# 8ModuleBoard_vr2.net
KiCad netlist of a schematic drawn in EAGLE
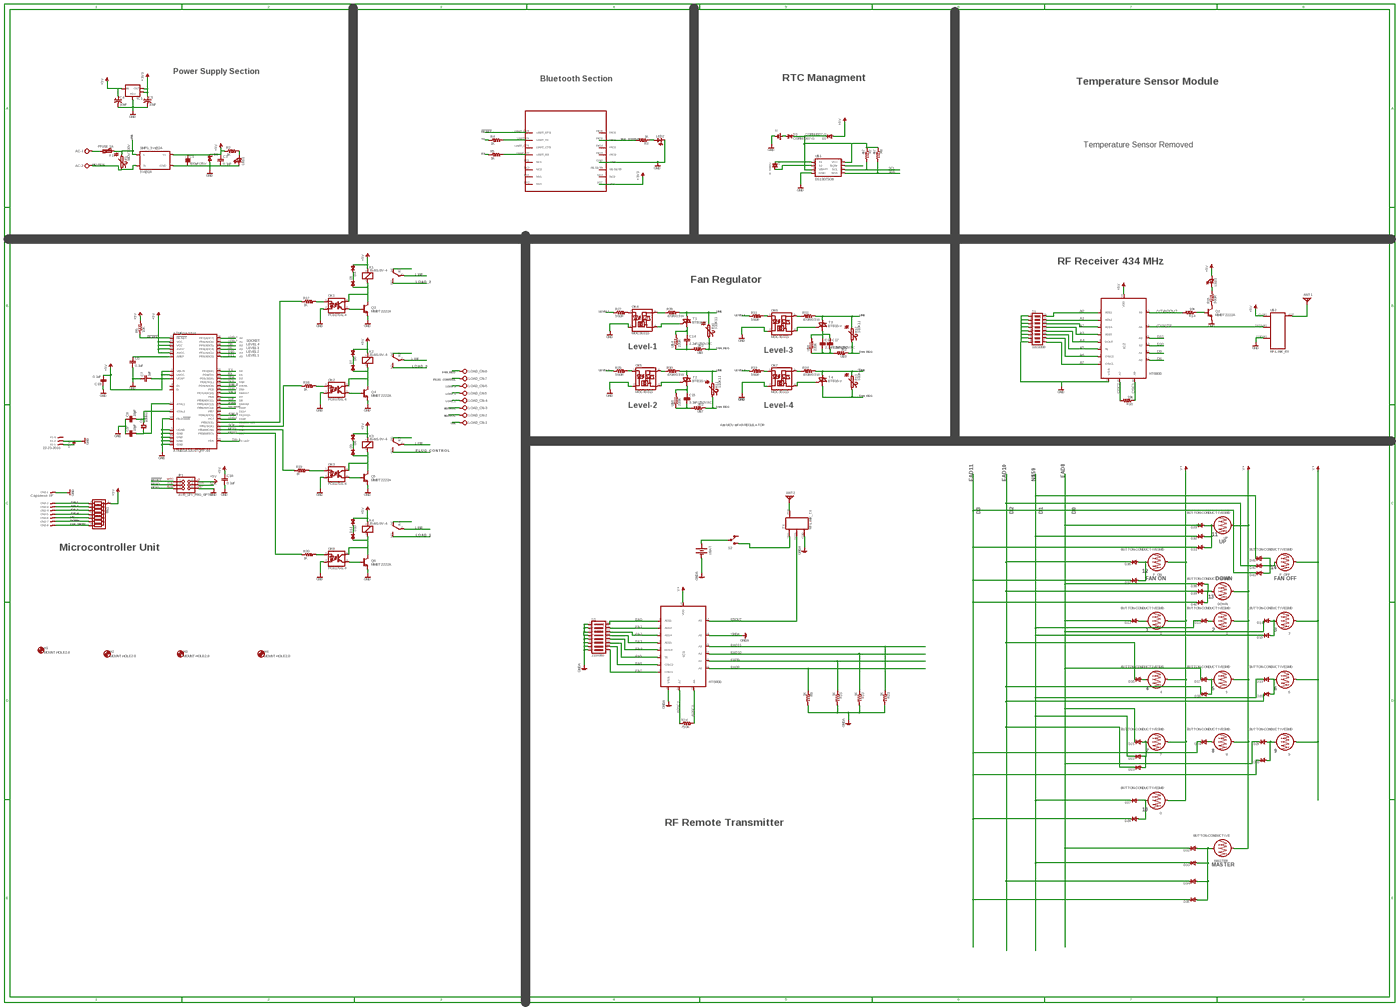
[diagram p0: schematic, sheet 1, overview]
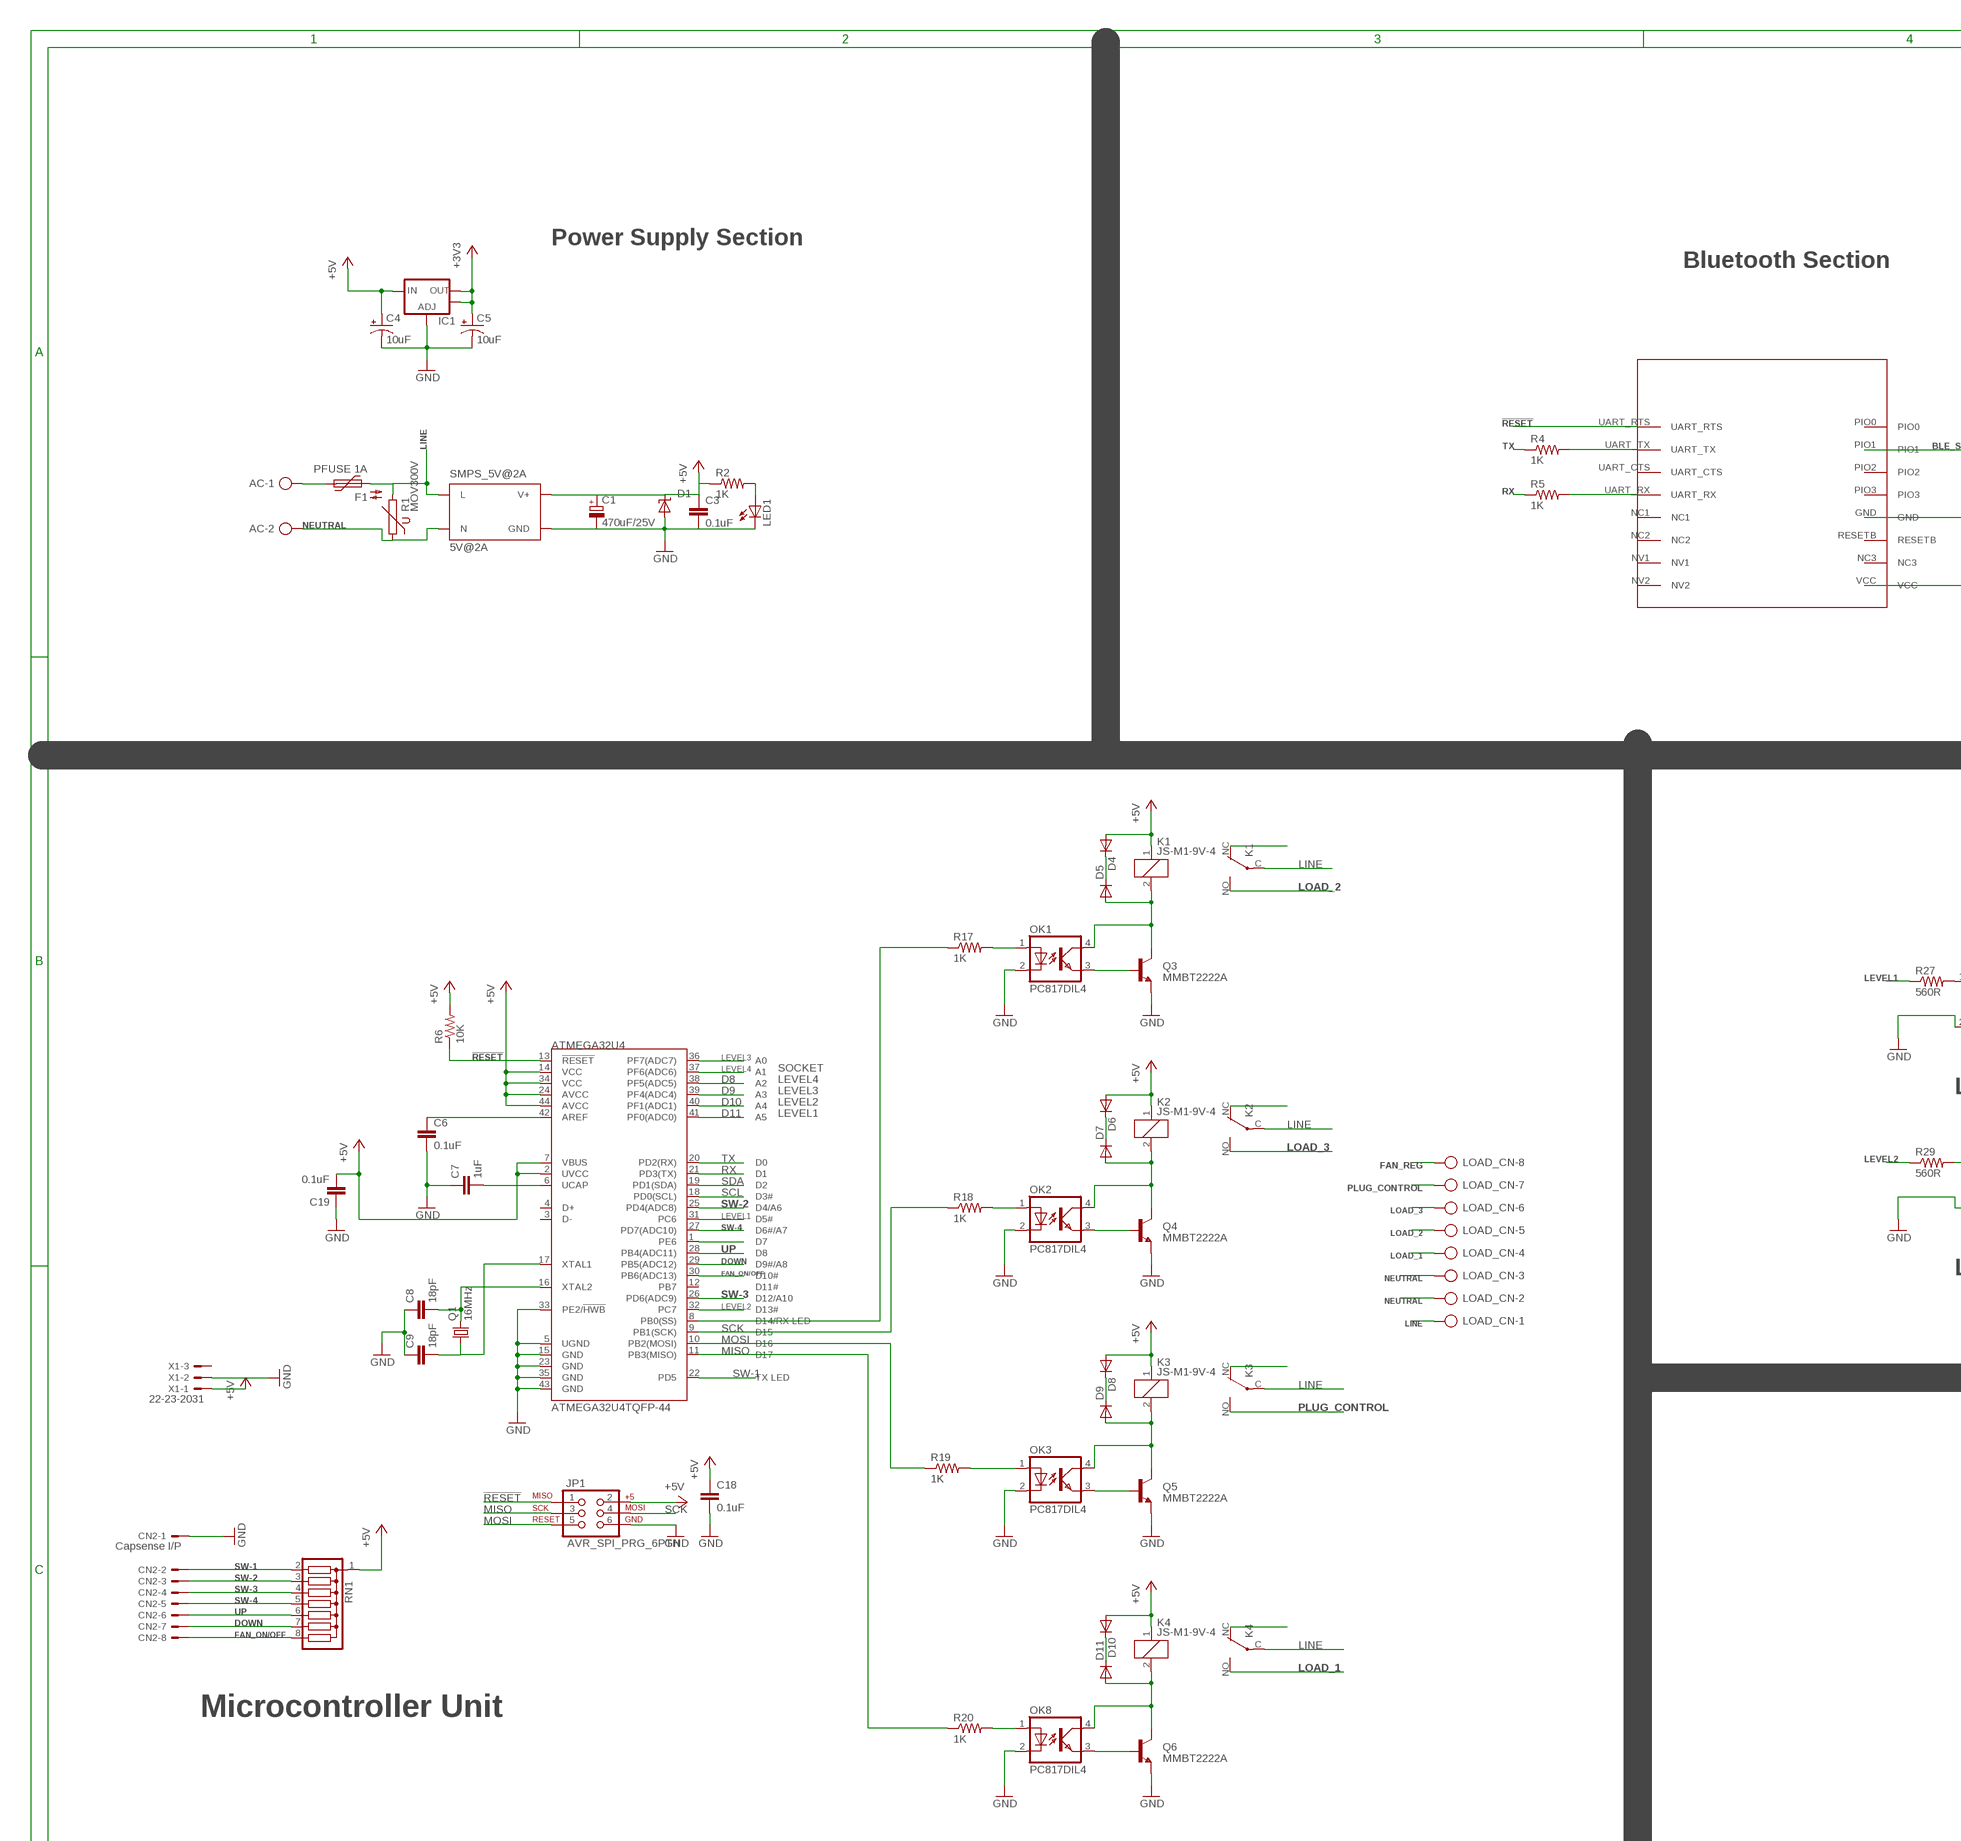
[diagram p1: schematic, sheet 1, part 1 of 4]
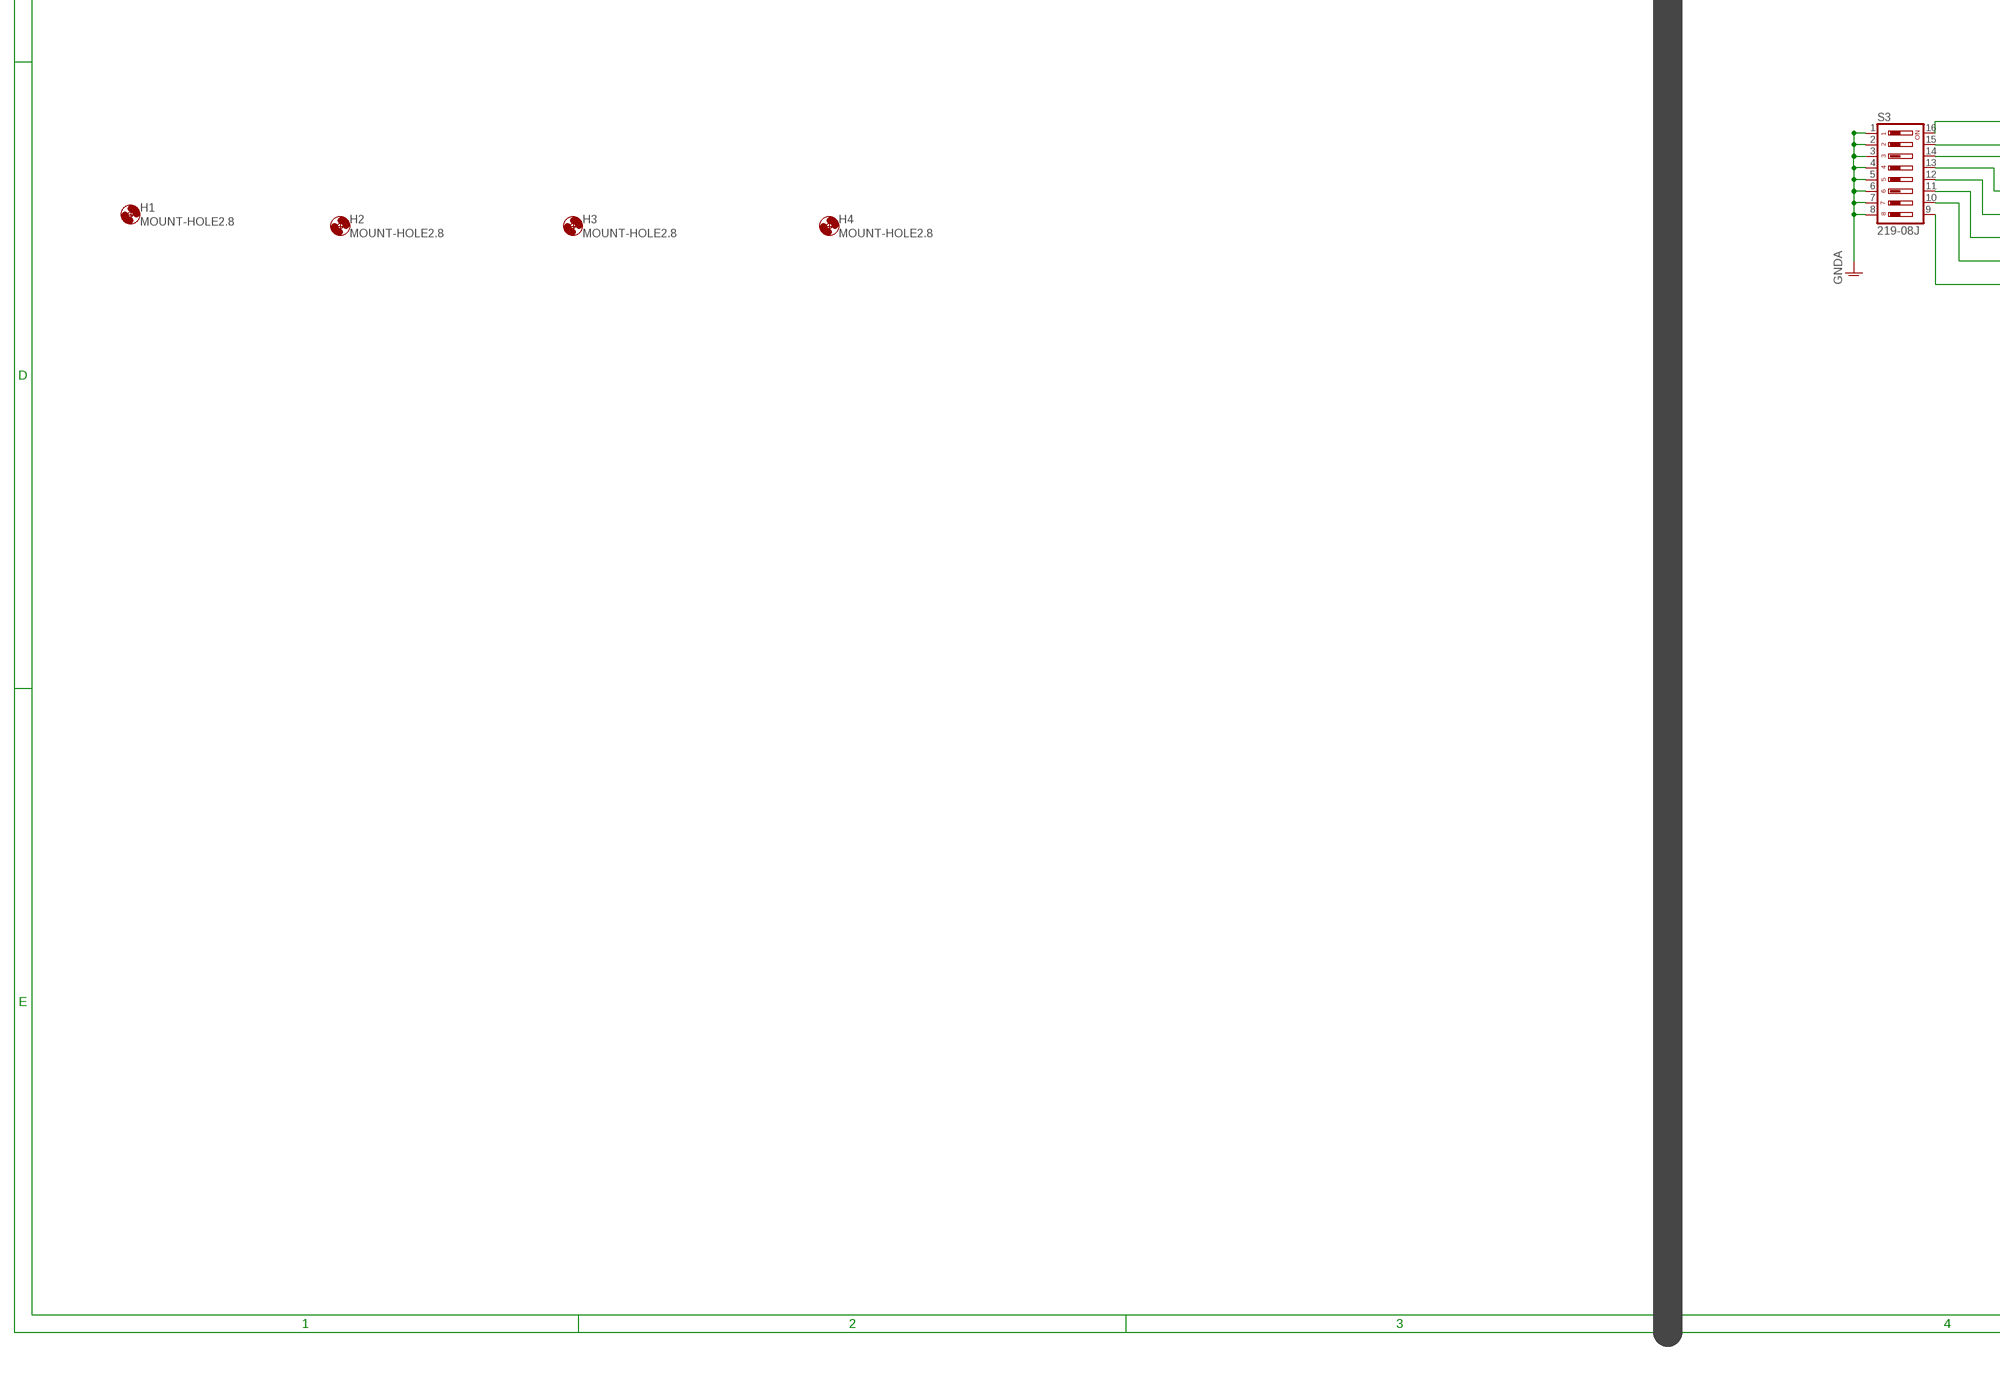
[diagram p2: schematic, sheet 1, part 2 of 4]
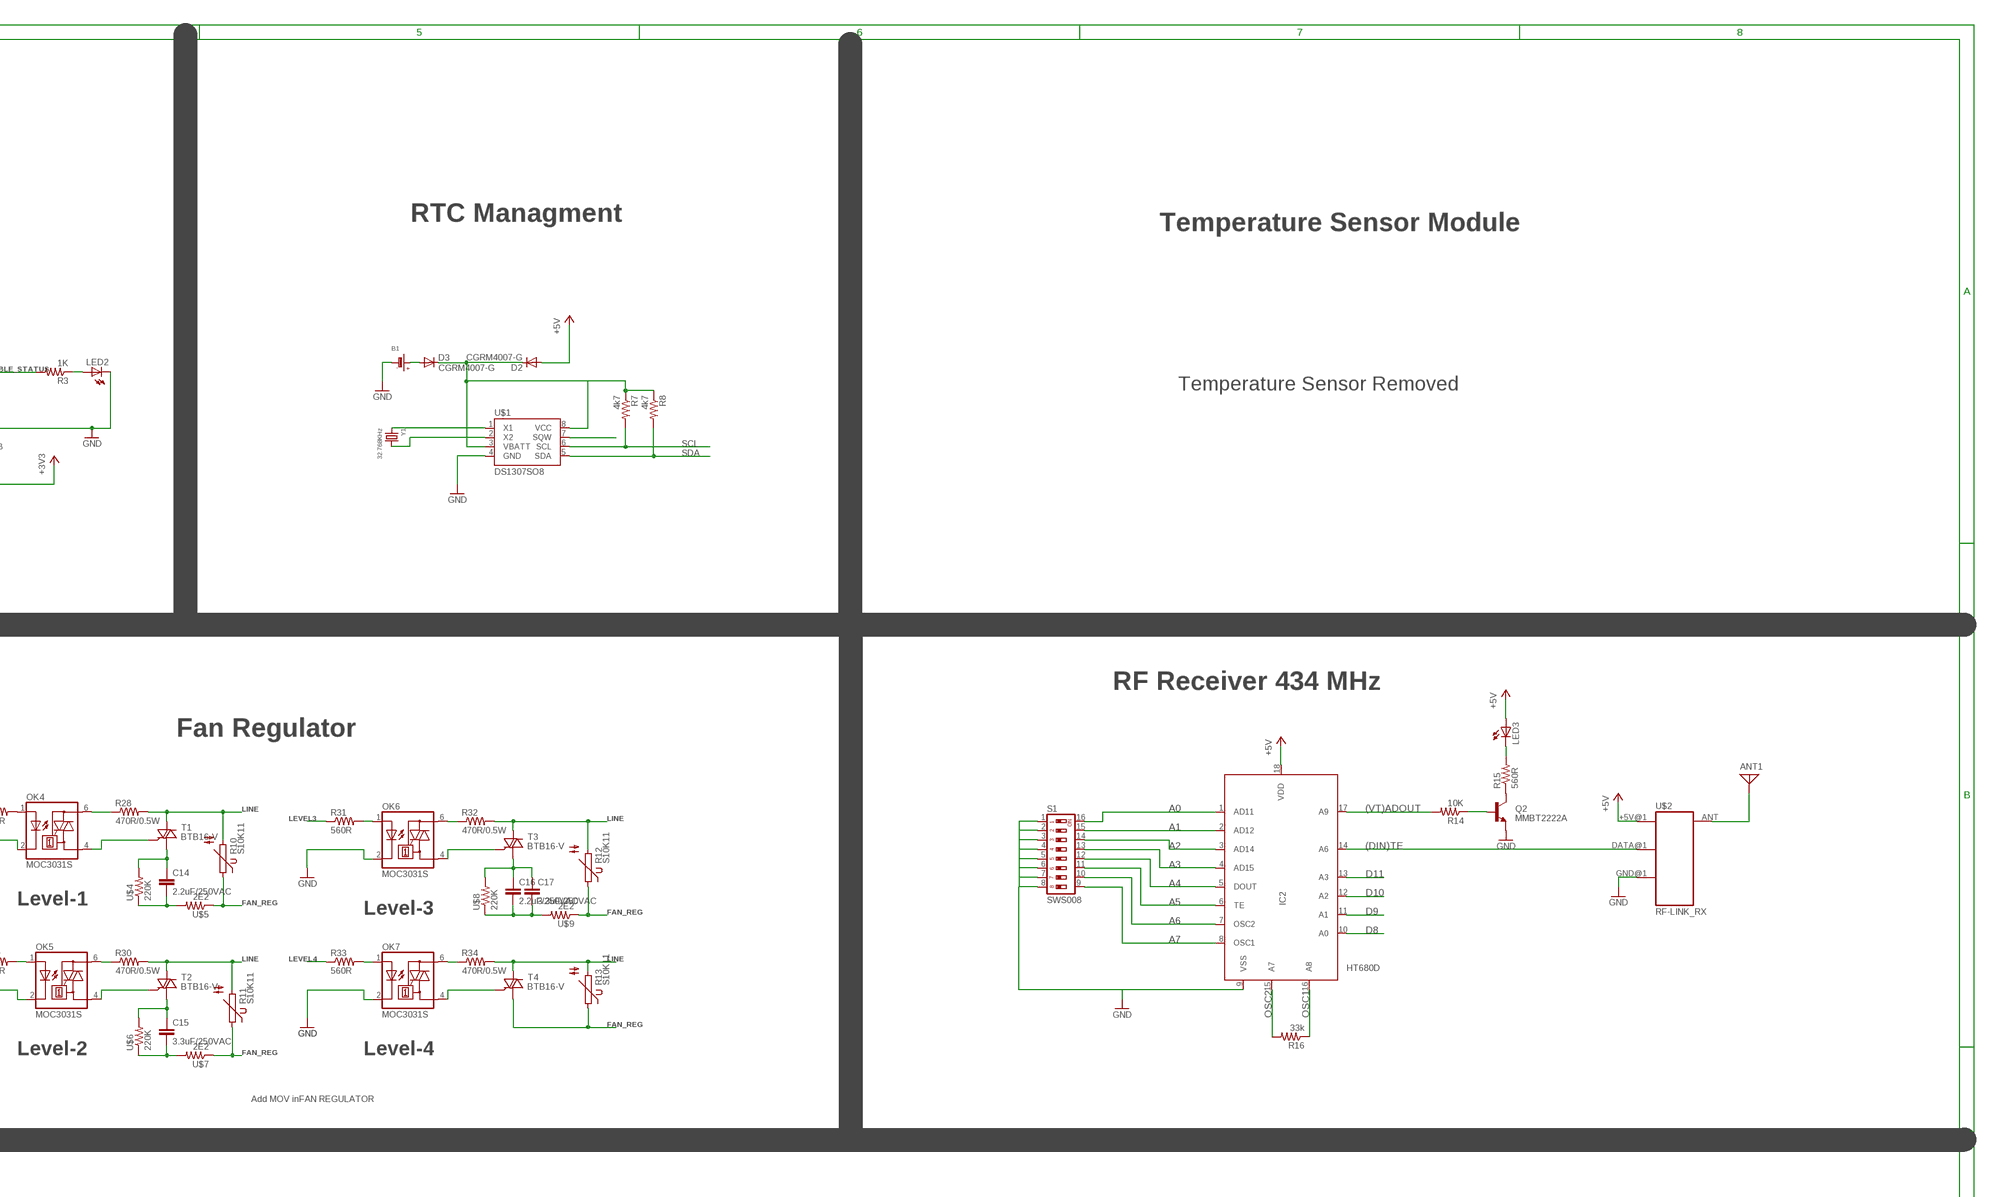
[diagram p3: schematic, sheet 1, part 3 of 4]
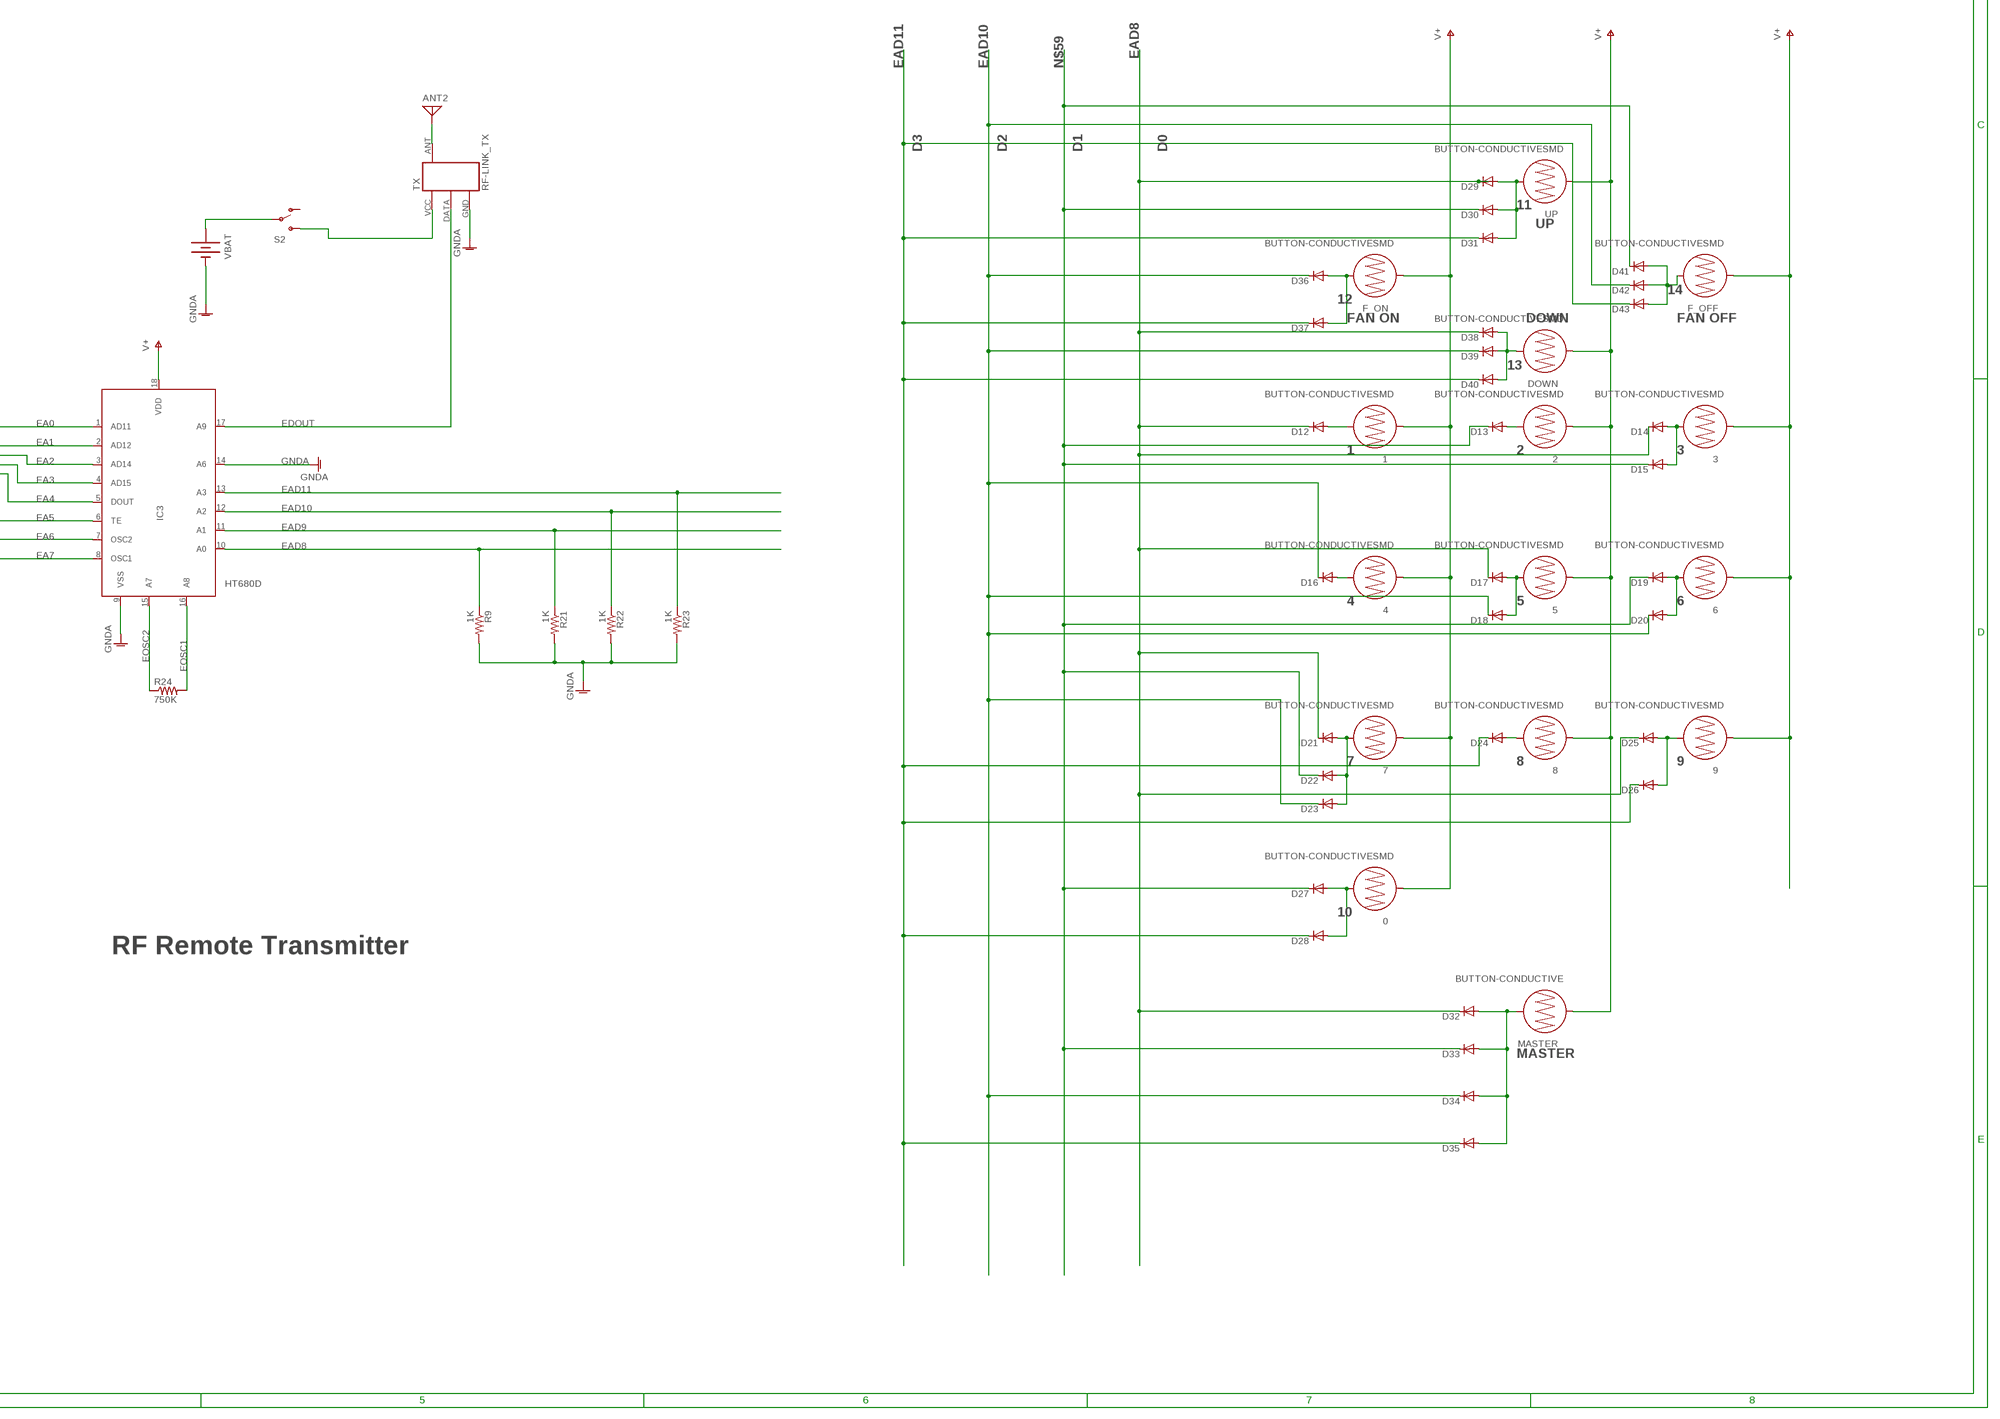
[diagram p4: schematic, sheet 1, part 4 of 4]

(export (version "E")
  (design (tool "Eeschema 10.0.6"))
  (components
    (comp (ref "0")
      (value "BUTTON-CONDUCTIVESMD")
      (footprint "eagle-import:BUTTON-CONDUCTIVE")
      (libsource (lib "eagle-import") (part "BUTTON-CONDUCTIVESMD"))
    )
    (comp (ref "1")
      (value "BUTTON-CONDUCTIVESMD")
      (footprint "eagle-import:BUTTON-CONDUCTIVE")
      (libsource (lib "eagle-import") (part "BUTTON-CONDUCTIVESMD"))
    )
    (comp (ref "2")
      (value "BUTTON-CONDUCTIVESMD")
      (footprint "eagle-import:BUTTON-CONDUCTIVE")
      (libsource (lib "eagle-import") (part "BUTTON-CONDUCTIVESMD"))
    )
    (comp (ref "3")
      (value "BUTTON-CONDUCTIVESMD")
      (footprint "eagle-import:BUTTON-CONDUCTIVE")
      (libsource (lib "eagle-import") (part "BUTTON-CONDUCTIVESMD"))
    )
    (comp (ref "4")
      (value "BUTTON-CONDUCTIVESMD")
      (footprint "eagle-import:BUTTON-CONDUCTIVE")
      (libsource (lib "eagle-import") (part "BUTTON-CONDUCTIVESMD"))
    )
    (comp (ref "5")
      (value "BUTTON-CONDUCTIVESMD")
      (footprint "eagle-import:BUTTON-CONDUCTIVE")
      (libsource (lib "eagle-import") (part "BUTTON-CONDUCTIVESMD"))
    )
    (comp (ref "6")
      (value "BUTTON-CONDUCTIVESMD")
      (footprint "eagle-import:BUTTON-CONDUCTIVE")
      (libsource (lib "eagle-import") (part "BUTTON-CONDUCTIVESMD"))
    )
    (comp (ref "7")
      (value "BUTTON-CONDUCTIVESMD")
      (footprint "eagle-import:BUTTON-CONDUCTIVE")
      (libsource (lib "eagle-import") (part "BUTTON-CONDUCTIVESMD"))
    )
    (comp (ref "8")
      (value "BUTTON-CONDUCTIVESMD")
      (footprint "eagle-import:BUTTON-CONDUCTIVE")
      (libsource (lib "eagle-import") (part "BUTTON-CONDUCTIVESMD"))
    )
    (comp (ref "9")
      (value "BUTTON-CONDUCTIVESMD")
      (footprint "eagle-import:BUTTON-CONDUCTIVE")
      (libsource (lib "eagle-import") (part "BUTTON-CONDUCTIVESMD"))
    )
    (comp (ref "AC")
      (value "AK300/2")
      (footprint "eagle-import:AK300_2")
      (libsource (lib "eagle-import") (part "AK300/2"))
    )
    (comp (ref "ANT1")
      (value "ANTENNA")
      (footprint "eagle-import:PAD-01")
      (libsource (lib "eagle-import") (part "ANTENNA"))
    )
    (comp (ref "ANT2")
      (value "ANTENNA")
      (footprint "eagle-import:PAD-01")
      (libsource (lib "eagle-import") (part "ANTENNA"))
    )
    (comp (ref "ATMEGA32U4")
      (value "ATMEGA32U4TQFP-44")
      (footprint "eagle-import:TQFP44")
      (libsource (lib "eagle-import") (part "ATMEGA32U4TQFP-44"))
    )
    (comp (ref "B1")
      (value "BATTERYCR2032")
      (footprint "eagle-import:CR2032")
      (libsource (lib "eagle-import") (part "BATTERYCR2032"))
    )
    (comp (ref "C1")
      (value "470uF/25V")
      (footprint "eagle-import:E5-8,5")
      (libsource (lib "eagle-import") (part "CPOL-EUE5-8.5"))
    )
    (comp (ref "C3")
      (value "0.1uF")
      (footprint "eagle-import:1206")
      (libsource (lib "eagle-import") (part "1.0UF50V10%(1206)"))
    )
    (comp (ref "C4")
      (value "10uF")
      (footprint "eagle-import:EIA3216")
      (libsource (lib "eagle-import") (part "10UF-16V-10%(TANT)"))
    )
    (comp (ref "C5")
      (value "10uF")
      (footprint "eagle-import:EIA3216")
      (libsource (lib "eagle-import") (part "10UF-16V-10%(TANT)"))
    )
    (comp (ref "C6")
      (value "0.1uF")
      (footprint "eagle-import:1206")
      (libsource (lib "eagle-import") (part "CAP1206"))
    )
    (comp (ref "C7")
      (value "1uF")
      (footprint "eagle-import:1206")
      (libsource (lib "eagle-import") (part "CAP1206"))
    )
    (comp (ref "C8")
      (value "18pF")
      (footprint "eagle-import:1206")
      (libsource (lib "eagle-import") (part "CAP1206"))
    )
    (comp (ref "C9")
      (value "18pF")
      (footprint "eagle-import:1206")
      (libsource (lib "eagle-import") (part "CAP1206"))
    )
    (comp (ref "C14")
      (value "2.2uF/250VAC")
      (footprint "eagle-import:C27.5B9")
      (libsource (lib "eagle-import") (part "C27/9"))
    )
    (comp (ref "C15")
      (value "3.3uF/250VAC")
      (footprint "eagle-import:C27.5B9")
      (libsource (lib "eagle-import") (part "C27/9"))
    )
    (comp (ref "C16")
      (value "2.2uF/250VAC")
      (footprint "eagle-import:C27.5B9")
      (libsource (lib "eagle-import") (part "C27/9"))
    )
    (comp (ref "C17")
      (value "3.3uF/250VAC")
      (footprint "eagle-import:C27.5B9")
      (libsource (lib "eagle-import") (part "C27/9"))
    )
    (comp (ref "C18")
      (value "0.1uF")
      (footprint "eagle-import:1206")
      (libsource (lib "eagle-import") (part "CAP1206"))
    )
    (comp (ref "C19")
      (value "0.1uF")
      (footprint "eagle-import:1206")
      (libsource (lib "eagle-import") (part "CAP1206"))
    )
    (comp (ref "CN2")
      (value "Capsense I/P")
      (footprint "eagle-import:22-23-2081")
      (fields (field (name "MF") "MOLEX") (field (name "MPN") "22-23-2081"))
      (libsource (lib "eagle-import") (part "22-23-2081"))
    )
    (comp (ref "D1")
      (value "SUPPRESSOR-SMBJ")
      (footprint "eagle-import:SMBJ")
      (libsource (lib "eagle-import") (part "SUPPRESSOR-SMBJ"))
    )
    (comp (ref "D2")
      (value "CGRM4007-G")
      (footprint "eagle-import:SOD-123_MINI-SMA")
      (libsource (lib "eagle-import") (part "CGRM400-G7"))
    )
    (comp (ref "D3")
      (value "CGRM4007-G")
      (footprint "eagle-import:SOD-123_MINI-SMA")
      (libsource (lib "eagle-import") (part "CGRM400-G7"))
    )
    (comp (ref "D4")
      (value "DIODE-SOD123")
      (footprint "eagle-import:SOD123")
      (libsource (lib "eagle-import") (part "DIODE-SOD123"))
    )
    (comp (ref "D5")
      (value "DIODE-SOD123")
      (footprint "eagle-import:SOD123")
      (libsource (lib "eagle-import") (part "DIODE-SOD123"))
    )
    (comp (ref "D6")
      (value "DIODE-SOD123")
      (footprint "eagle-import:SOD123")
      (libsource (lib "eagle-import") (part "DIODE-SOD123"))
    )
    (comp (ref "D7")
      (value "DIODE-SOD123")
      (footprint "eagle-import:SOD123")
      (libsource (lib "eagle-import") (part "DIODE-SOD123"))
    )
    (comp (ref "D8")
      (value "DIODE-SOD123")
      (footprint "eagle-import:SOD123")
      (libsource (lib "eagle-import") (part "DIODE-SOD123"))
    )
    (comp (ref "D9")
      (value "DIODE-SOD123")
      (footprint "eagle-import:SOD123")
      (libsource (lib "eagle-import") (part "DIODE-SOD123"))
    )
    (comp (ref "D10")
      (value "DIODE-SOD123")
      (footprint "eagle-import:SOD123")
      (libsource (lib "eagle-import") (part "DIODE-SOD123"))
    )
    (comp (ref "D11")
      (value "DIODE-SOD123")
      (footprint "eagle-import:SOD123")
      (libsource (lib "eagle-import") (part "DIODE-SOD123"))
    )
    (comp (ref "D12")
      (value "DIODE-SOD123")
      (footprint "eagle-import:SOD123")
      (libsource (lib "eagle-import") (part "DIODE-SOD123"))
    )
    (comp (ref "D13")
      (value "DIODE-SOD123")
      (footprint "eagle-import:SOD123")
      (libsource (lib "eagle-import") (part "DIODE-SOD123"))
    )
    (comp (ref "D14")
      (value "DIODE-SOD123")
      (footprint "eagle-import:SOD123")
      (libsource (lib "eagle-import") (part "DIODE-SOD123"))
    )
    (comp (ref "D15")
      (value "DIODE-SOD123")
      (footprint "eagle-import:SOD123")
      (libsource (lib "eagle-import") (part "DIODE-SOD123"))
    )
    (comp (ref "D16")
      (value "DIODE-SOD123")
      (footprint "eagle-import:SOD123")
      (libsource (lib "eagle-import") (part "DIODE-SOD123"))
    )
    (comp (ref "D17")
      (value "DIODE-SOD123")
      (footprint "eagle-import:SOD123")
      (libsource (lib "eagle-import") (part "DIODE-SOD123"))
    )
    (comp (ref "D18")
      (value "DIODE-SOD123")
      (footprint "eagle-import:SOD123")
      (libsource (lib "eagle-import") (part "DIODE-SOD123"))
    )
    (comp (ref "D19")
      (value "DIODE-SOD123")
      (footprint "eagle-import:SOD123")
      (libsource (lib "eagle-import") (part "DIODE-SOD123"))
    )
    (comp (ref "D20")
      (value "DIODE-SOD123")
      (footprint "eagle-import:SOD123")
      (libsource (lib "eagle-import") (part "DIODE-SOD123"))
    )
    (comp (ref "D21")
      (value "DIODE-SOD123")
      (footprint "eagle-import:SOD123")
      (libsource (lib "eagle-import") (part "DIODE-SOD123"))
    )
    (comp (ref "D22")
      (value "DIODE-SOD123")
      (footprint "eagle-import:SOD123")
      (libsource (lib "eagle-import") (part "DIODE-SOD123"))
    )
    (comp (ref "D23")
      (value "DIODE-SOD123")
      (footprint "eagle-import:SOD123")
      (libsource (lib "eagle-import") (part "DIODE-SOD123"))
    )
    (comp (ref "D24")
      (value "DIODE-SOD123")
      (footprint "eagle-import:SOD123")
      (libsource (lib "eagle-import") (part "DIODE-SOD123"))
    )
    (comp (ref "D25")
      (value "DIODE-SOD123")
      (footprint "eagle-import:SOD123")
      (libsource (lib "eagle-import") (part "DIODE-SOD123"))
    )
    (comp (ref "D26")
      (value "DIODE-SOD123")
      (footprint "eagle-import:SOD123")
      (libsource (lib "eagle-import") (part "DIODE-SOD123"))
    )
    (comp (ref "D27")
      (value "DIODE-SOD123")
      (footprint "eagle-import:SOD123")
      (libsource (lib "eagle-import") (part "DIODE-SOD123"))
    )
    (comp (ref "D28")
      (value "DIODE-SOD123")
      (footprint "eagle-import:SOD123")
      (libsource (lib "eagle-import") (part "DIODE-SOD123"))
    )
    (comp (ref "D29")
      (value "DIODE-SOD123")
      (footprint "eagle-import:SOD123")
      (libsource (lib "eagle-import") (part "DIODE-SOD123"))
    )
    (comp (ref "D30")
      (value "DIODE-SOD123")
      (footprint "eagle-import:SOD123")
      (libsource (lib "eagle-import") (part "DIODE-SOD123"))
    )
    (comp (ref "D31")
      (value "DIODE-SOD123")
      (footprint "eagle-import:SOD123")
      (libsource (lib "eagle-import") (part "DIODE-SOD123"))
    )
    (comp (ref "D32")
      (value "DIODE-SOD123")
      (footprint "eagle-import:SOD123")
      (libsource (lib "eagle-import") (part "DIODE-SOD123"))
    )
    (comp (ref "D33")
      (value "DIODE-SOD123")
      (footprint "eagle-import:SOD123")
      (libsource (lib "eagle-import") (part "DIODE-SOD123"))
    )
    (comp (ref "D34")
      (value "DIODE-SOD123")
      (footprint "eagle-import:SOD123")
      (libsource (lib "eagle-import") (part "DIODE-SOD123"))
    )
    (comp (ref "D35")
      (value "DIODE-SOD123")
      (footprint "eagle-import:SOD123")
      (libsource (lib "eagle-import") (part "DIODE-SOD123"))
    )
    (comp (ref "D36")
      (value "DIODE-SOD123")
      (footprint "eagle-import:SOD123")
      (libsource (lib "eagle-import") (part "DIODE-SOD123"))
    )
    (comp (ref "D37")
      (value "DIODE-SOD123")
      (footprint "eagle-import:SOD123")
      (libsource (lib "eagle-import") (part "DIODE-SOD123"))
    )
    (comp (ref "D38")
      (value "DIODE-SOD123")
      (footprint "eagle-import:SOD123")
      (libsource (lib "eagle-import") (part "DIODE-SOD123"))
    )
    (comp (ref "D39")
      (value "DIODE-SOD123")
      (footprint "eagle-import:SOD123")
      (libsource (lib "eagle-import") (part "DIODE-SOD123"))
    )
    (comp (ref "D40")
      (value "DIODE-SOD123")
      (footprint "eagle-import:SOD123")
      (libsource (lib "eagle-import") (part "DIODE-SOD123"))
    )
    (comp (ref "D41")
      (value "DIODE-SOD123")
      (footprint "eagle-import:SOD123")
      (libsource (lib "eagle-import") (part "DIODE-SOD123"))
    )
    (comp (ref "D42")
      (value "DIODE-SOD123")
      (footprint "eagle-import:SOD123")
      (libsource (lib "eagle-import") (part "DIODE-SOD123"))
    )
    (comp (ref "D43")
      (value "DIODE-SOD123")
      (footprint "eagle-import:SOD123")
      (libsource (lib "eagle-import") (part "DIODE-SOD123"))
    )
    (comp (ref "DOWN")
      (value "BUTTON-CONDUCTIVESMD")
      (footprint "eagle-import:BUTTON-CONDUCTIVE")
      (libsource (lib "eagle-import") (part "BUTTON-CONDUCTIVESMD"))
    )
    (comp (ref "F1")
      (value "PFUSE 1A")
      (footprint "eagle-import:MF-5,1B")
      (libsource (lib "eagle-import") (part "MF-R055-5,1B"))
    )
    (comp (ref "F_OFF")
      (value "BUTTON-CONDUCTIVESMD")
      (footprint "eagle-import:BUTTON-CONDUCTIVE")
      (libsource (lib "eagle-import") (part "BUTTON-CONDUCTIVESMD"))
    )
    (comp (ref "F_ON")
      (value "BUTTON-CONDUCTIVESMD")
      (footprint "eagle-import:BUTTON-CONDUCTIVE")
      (libsource (lib "eagle-import") (part "BUTTON-CONDUCTIVESMD"))
    )
    (comp (ref "H1")
      (value "MOUNT-HOLE2.8")
      (footprint "eagle-import:2,8")
      (libsource (lib "eagle-import") (part "MOUNT-HOLE2.8"))
    )
    (comp (ref "H2")
      (value "MOUNT-HOLE2.8")
      (footprint "eagle-import:2,8")
      (libsource (lib "eagle-import") (part "MOUNT-HOLE2.8"))
    )
    (comp (ref "H3")
      (value "MOUNT-HOLE2.8")
      (footprint "eagle-import:2,8")
      (libsource (lib "eagle-import") (part "MOUNT-HOLE2.8"))
    )
    (comp (ref "H4")
      (value "MOUNT-HOLE2.8")
      (footprint "eagle-import:2,8")
      (libsource (lib "eagle-import") (part "MOUNT-HOLE2.8"))
    )
    (comp (ref "IC1")
      (value "V_REG_LM1117SOT223")
      (footprint "eagle-import:SOT223")
      (libsource (lib "eagle-import") (part "V_REG_LM1117SOT223"))
    )
    (comp (ref "IC2")
      (value "HT680D")
      (footprint "eagle-import:SOP18")
      (libsource (lib "eagle-import") (part "HT680D"))
    )
    (comp (ref "IC3")
      (value "HT680D")
      (footprint "eagle-import:SOP18")
      (libsource (lib "eagle-import") (part "HT680D"))
    )
    (comp (ref "JP1")
      (value "AVR_SPI_PRG_6PTH")
      (footprint "eagle-import:2X3")
      (libsource (lib "eagle-import") (part "AVR_SPI_PRG_6PTH"))
    )
    (comp (ref "K1")
      (value "JS-M1-9V-4")
      (footprint "eagle-import:JS-M")
      (libsource (lib "eagle-import") (part "JS-M1-9V-4"))
    )
    (comp (ref "K2")
      (value "JS-M1-9V-4")
      (footprint "eagle-import:JS-M")
      (libsource (lib "eagle-import") (part "JS-M1-9V-4"))
    )
    (comp (ref "K3")
      (value "JS-M1-9V-4")
      (footprint "eagle-import:JS-M")
      (libsource (lib "eagle-import") (part "JS-M1-9V-4"))
    )
    (comp (ref "K4")
      (value "JS-M1-9V-4")
      (footprint "eagle-import:JS-M")
      (libsource (lib "eagle-import") (part "JS-M1-9V-4"))
    )
    (comp (ref "LED1")
      (value "LEDSML1206")
      (footprint "eagle-import:SML1206")
      (libsource (lib "eagle-import") (part "LEDSML1206"))
    )
    (comp (ref "LED2")
      (value "LEDSML1206")
      (footprint "eagle-import:SML1206")
      (libsource (lib "eagle-import") (part "LEDSML1206"))
    )
    (comp (ref "LED3")
      (value "LEDSML1206")
      (footprint "eagle-import:SML1206")
      (libsource (lib "eagle-import") (part "LEDSML1206"))
    )
    (comp (ref "LOAD_CN")
      (value "AK300/8")
      (footprint "eagle-import:AK300_8")
      (libsource (lib "eagle-import") (part "AK300/8"))
    )
    (comp (ref "MASTER")
      (value "BUTTON-CONDUCTIVE")
      (footprint "eagle-import:BUTTON-CONDUCTIVE-MINI")
      (libsource (lib "eagle-import") (part "BUTTON-CONDUCTIVE"))
    )
    (comp (ref "OK1")
      (value "PC817DIL4")
      (footprint "eagle-import:DIL4-SMD")
      (libsource (lib "eagle-import") (part "PC817DIL4"))
    )
    (comp (ref "OK2")
      (value "PC817DIL4")
      (footprint "eagle-import:DIL4-SMD")
      (libsource (lib "eagle-import") (part "PC817DIL4"))
    )
    (comp (ref "OK3")
      (value "PC817DIL4")
      (footprint "eagle-import:DIL4-SMD")
      (libsource (lib "eagle-import") (part "PC817DIL4"))
    )
    (comp (ref "OK4")
      (value "MOC3031S")
      (footprint "eagle-import:DIL6-SMD")
      (fields (field (name "MF") "FAIRCHILD SEMICONDUCTOR") (field (name "MPN") "MOC3031SM"))
      (libsource (lib "eagle-import") (part "MOC30S31"))
    )
    (comp (ref "OK5")
      (value "MOC3031S")
      (footprint "eagle-import:DIL6-SMD")
      (fields
        (field (name "MF") "FAIRCHILD SEMICONDUCTOR")
        (field (name "MPN") "MOC3031SM")
        (field (name "MF_1") "FAIRCHILD SEMICONDUCTOR")
        (field (name "MPN_1") "MOC3031SM")
        (field (name "OC_FARNELL") "unknown")
        (field (name "OC_NEWARK") "34C1335")
      )
      (libsource (lib "eagle-import") (part "MOC30S31"))
    )
    (comp (ref "OK6")
      (value "MOC3031S")
      (footprint "eagle-import:DIL6-SMD")
      (fields
        (field (name "MF") "FAIRCHILD SEMICONDUCTOR")
        (field (name "MPN") "MOC3031SM")
        (field (name "MF_1") "FAIRCHILD SEMICONDUCTOR")
        (field (name "MPN_1") "MOC3031SM")
        (field (name "OC_FARNELL") "unknown")
        (field (name "OC_NEWARK") "34C1335")
      )
      (libsource (lib "eagle-import") (part "MOC30S31"))
    )
    (comp (ref "OK7")
      (value "MOC3031S")
      (footprint "eagle-import:DIL6-SMD")
      (fields
        (field (name "MF") "FAIRCHILD SEMICONDUCTOR")
        (field (name "MPN") "MOC3031SM")
        (field (name "MF_1") "FAIRCHILD SEMICONDUCTOR")
        (field (name "MPN_1") "MOC3031SM")
        (field (name "OC_FARNELL") "unknown")
        (field (name "OC_NEWARK") "34C1335")
      )
      (libsource (lib "eagle-import") (part "MOC30S31"))
    )
    (comp (ref "OK8")
      (value "PC817DIL4")
      (footprint "eagle-import:DIL4-SMD")
      (libsource (lib "eagle-import") (part "PC817DIL4"))
    )
    (comp (ref "Q1")
      (value "16MHz")
      (footprint "eagle-import:HC49UP")
      (libsource (lib "eagle-import") (part "CRYSTALHC49UP"))
    )
    (comp (ref "Q2")
      (value "MMBT2222A")
      (footprint "eagle-import:SOT23-3")
      (libsource (lib "eagle-import") (part "TRANSISTOR_NPNMMBT2222A"))
    )
    (comp (ref "Q3")
      (value "MMBT2222A")
      (footprint "eagle-import:SOT23-3")
      (fields (field (name "PROD_ID") "TRANS-08049"))
      (libsource (lib "eagle-import") (part "TRANSISTOR_NPNMMBT2222A"))
    )
    (comp (ref "Q4")
      (value "MMBT2222A")
      (footprint "eagle-import:SOT23-3")
      (fields (field (name "PROD_ID") "TRANS-08049"))
      (libsource (lib "eagle-import") (part "TRANSISTOR_NPNMMBT2222A"))
    )
    (comp (ref "Q5")
      (value "MMBT2222A")
      (footprint "eagle-import:SOT23-3")
      (fields (field (name "PROD_ID") "TRANS-08049"))
      (libsource (lib "eagle-import") (part "TRANSISTOR_NPNMMBT2222A"))
    )
    (comp (ref "Q6")
      (value "MMBT2222A")
      (footprint "eagle-import:SOT23-3")
      (fields (field (name "PROD_ID") "TRANS-08049"))
      (libsource (lib "eagle-import") (part "TRANSISTOR_NPNMMBT2222A"))
    )
    (comp (ref "R1")
      (value "MOV300V")
      (footprint "eagle-import:S10K11")
      (libsource (lib "eagle-import") (part "S10K11"))
    )
    (comp (ref "R2")
      (value "1K")
      (footprint "eagle-import:1206")
      (libsource (lib "eagle-import") (part "SparkFun-Resistors_RESISTOR1206"))
    )
    (comp (ref "R3")
      (value "1K")
      (footprint "eagle-import:1206")
      (libsource (lib "eagle-import") (part "RESISTOR1206"))
    )
    (comp (ref "R4")
      (value "1K")
      (footprint "eagle-import:1206")
      (libsource (lib "eagle-import") (part "SparkFun-Resistors_RESISTOR1206"))
    )
    (comp (ref "R5")
      (value "1K")
      (footprint "eagle-import:1206")
      (libsource (lib "eagle-import") (part "SparkFun-Resistors_RESISTOR1206"))
    )
    (comp (ref "R6")
      (value "10K")
      (footprint "eagle-import:1206")
      (libsource (lib "eagle-import") (part "RESISTOR1206"))
    )
    (comp (ref "R7")
      (value "4k7")
      (footprint "eagle-import:1206")
      (libsource (lib "eagle-import") (part "RESISTOR1206"))
    )
    (comp (ref "R8")
      (value "4k7")
      (footprint "eagle-import:1206")
      (libsource (lib "eagle-import") (part "RESISTOR1206"))
    )
    (comp (ref "R9")
      (value "1K")
      (footprint "eagle-import:1206")
      (libsource (lib "eagle-import") (part "RESISTOR1206"))
    )
    (comp (ref "R10")
      (value "S10K11")
      (footprint "eagle-import:S10K11")
      (libsource (lib "eagle-import") (part "S10K11"))
    )
    (comp (ref "R11")
      (value "S10K11")
      (footprint "eagle-import:S10K11")
      (libsource (lib "eagle-import") (part "S10K11"))
    )
    (comp (ref "R12")
      (value "S10K11")
      (footprint "eagle-import:S10K11")
      (libsource (lib "eagle-import") (part "S10K11"))
    )
    (comp (ref "R13")
      (value "S10K11")
      (footprint "eagle-import:S10K11")
      (libsource (lib "eagle-import") (part "S10K11"))
    )
    (comp (ref "R14")
      (value "10K")
      (footprint "eagle-import:1206")
      (libsource (lib "eagle-import") (part "RESISTOR1206"))
    )
    (comp (ref "R15")
      (value "560R")
      (footprint "eagle-import:1206")
      (libsource (lib "eagle-import") (part "SparkFun-Resistors_RESISTOR1206"))
    )
    (comp (ref "R16")
      (value "33k")
      (footprint "eagle-import:1206")
      (libsource (lib "eagle-import") (part "SparkFun-Resistors_RESISTOR1206"))
    )
    (comp (ref "R17")
      (value "1K")
      (footprint "eagle-import:1206")
      (libsource (lib "eagle-import") (part "SparkFun-Resistors_RESISTOR1206"))
    )
    (comp (ref "R18")
      (value "1K")
      (footprint "eagle-import:1206")
      (libsource (lib "eagle-import") (part "SparkFun-Resistors_RESISTOR1206"))
    )
    (comp (ref "R19")
      (value "1K")
      (footprint "eagle-import:1206")
      (libsource (lib "eagle-import") (part "SparkFun-Resistors_RESISTOR1206"))
    )
    (comp (ref "R20")
      (value "1K")
      (footprint "eagle-import:1206")
      (libsource (lib "eagle-import") (part "SparkFun-Resistors_RESISTOR1206"))
    )
    (comp (ref "R21")
      (value "1K")
      (footprint "eagle-import:1206")
      (libsource (lib "eagle-import") (part "RESISTOR1206"))
    )
    (comp (ref "R22")
      (value "1K")
      (footprint "eagle-import:1206")
      (libsource (lib "eagle-import") (part "RESISTOR1206"))
    )
    (comp (ref "R23")
      (value "1K")
      (footprint "eagle-import:1206")
      (libsource (lib "eagle-import") (part "RESISTOR1206"))
    )
    (comp (ref "R24")
      (value "750K")
      (footprint "eagle-import:1206")
      (libsource (lib "eagle-import") (part "RESISTOR1206"))
    )
    (comp (ref "R27")
      (value "560R")
      (footprint "eagle-import:1206")
      (libsource (lib "eagle-import") (part "SparkFun-Resistors_RESISTOR1206"))
    )
    (comp (ref "R28")
      (value "470R/0.5W")
      (footprint "eagle-import:0411V")
      (libsource (lib "eagle-import") (part "R-US_0411/3V"))
    )
    (comp (ref "R29")
      (value "560R")
      (footprint "eagle-import:1206")
      (libsource (lib "eagle-import") (part "SparkFun-Resistors_RESISTOR1206"))
    )
    (comp (ref "R30")
      (value "470R/0.5W")
      (footprint "eagle-import:0411V")
      (libsource (lib "eagle-import") (part "R-US_0411/3V"))
    )
    (comp (ref "R31")
      (value "560R")
      (footprint "eagle-import:1206")
      (libsource (lib "eagle-import") (part "SparkFun-Resistors_RESISTOR1206"))
    )
    (comp (ref "R32")
      (value "470R/0.5W")
      (footprint "eagle-import:0411V")
      (libsource (lib "eagle-import") (part "R-US_0411/3V"))
    )
    (comp (ref "R33")
      (value "560R")
      (footprint "eagle-import:1206")
      (libsource (lib "eagle-import") (part "SparkFun-Resistors_RESISTOR1206"))
    )
    (comp (ref "R34")
      (value "470R/0.5W")
      (footprint "eagle-import:0411V")
      (libsource (lib "eagle-import") (part "R-US_0411/3V"))
    )
    (comp (ref "RN1")
      (value "G07R")
      (footprint "eagle-import:SIL8")
      (libsource (lib "eagle-import") (part "G07R"))
    )
    (comp (ref "S1")
      (value "SWS008")
      (footprint "eagle-import:SMS-008")
      (libsource (lib "eagle-import") (part "SWS008"))
    )
    (comp (ref "S2")
      (value "SWITCH-SPDT-SMD-A")
      (footprint "eagle-import:SWITCH-SPST-SMD-A")
      (libsource (lib "eagle-import") (part "SWITCH-SPDT-SMD-A"))
    )
    (comp (ref "S3")
      (value "219-08J")
      (footprint "eagle-import:CTS-219-08J")
      (libsource (lib "eagle-import") (part "219-08J"))
    )
    (comp (ref "SMPS_5V@2A")
      (value "5V@2A")
      (footprint "eagle-import:MKS1854-6-0-404")
      (libsource (lib "eagle-import") (part "MKS1854-6-0-404"))
    )
    (comp (ref "T1")
      (value "BTB16-V")
      (footprint "eagle-import:TO220BV")
      (libsource (lib "eagle-import") (part "BT138-V"))
    )
    (comp (ref "T2")
      (value "BTB16-V")
      (footprint "eagle-import:TO220BV")
      (libsource (lib "eagle-import") (part "BT138-V"))
    )
    (comp (ref "T3")
      (value "BTB16-V")
      (footprint "eagle-import:TO220BV")
      (libsource (lib "eagle-import") (part "BT138-V"))
    )
    (comp (ref "T4")
      (value "BTB16-V")
      (footprint "eagle-import:TO220BV")
      (libsource (lib "eagle-import") (part "BT138-V"))
    )
    (comp (ref "TX")
      (value "RF-LINK_TX")
      (footprint "eagle-import:RF-LINK_TX")
      (libsource (lib "eagle-import") (part "RF-LINK_TX"))
    )
    (comp (ref "U$1")
      (value "DS1307SO8")
      (footprint "eagle-import:SO08")
      (libsource (lib "eagle-import") (part "DS1307SO8"))
    )
    (comp (ref "U$2")
      (value "RF-LINK_RX")
      (footprint "eagle-import:RF-LINK_RX")
      (libsource (lib "eagle-import") (part "RF-LINK_RX"))
    )
    (comp (ref "U$3")
      (value "HM-11")
      (footprint "eagle-import:HM-11")
      (libsource (lib "eagle-import") (part "HM-11"))
    )
    (comp (ref "U$4")
      (value "220K")
      (footprint "eagle-import:1206")
      (libsource (lib "eagle-import") (part "SparkFun-Resistors_RESISTOR1206"))
    )
    (comp (ref "U$5")
      (value "2E2")
      (footprint "eagle-import:1206")
      (libsource (lib "eagle-import") (part "SparkFun-Resistors_RESISTOR1206"))
    )
    (comp (ref "U$6")
      (value "220K")
      (footprint "eagle-import:1206")
      (libsource (lib "eagle-import") (part "SparkFun-Resistors_RESISTOR1206"))
    )
    (comp (ref "U$7")
      (value "2E2")
      (footprint "eagle-import:1206")
      (libsource (lib "eagle-import") (part "SparkFun-Resistors_RESISTOR1206"))
    )
    (comp (ref "U$8")
      (value "220K")
      (footprint "eagle-import:1206")
      (libsource (lib "eagle-import") (part "SparkFun-Resistors_RESISTOR1206"))
    )
    (comp (ref "U$9")
      (value "2E2")
      (footprint "eagle-import:1206")
      (libsource (lib "eagle-import") (part "SparkFun-Resistors_RESISTOR1206"))
    )
    (comp (ref "UP")
      (value "BUTTON-CONDUCTIVESMD")
      (footprint "eagle-import:BUTTON-CONDUCTIVE")
      (libsource (lib "eagle-import") (part "BUTTON-CONDUCTIVESMD"))
    )
    (comp (ref "VBAT")
      (value "BATTERY20SMD")
      (footprint "eagle-import:BATTCON_20MM")
      (libsource (lib "eagle-import") (part "BATTERY20SMD"))
    )
    (comp (ref "X1")
      (value "22-23-2031")
      (footprint "eagle-import:22-23-2031")
      (fields (field (name "MF") "MOLEX"))
      (libsource (lib "eagle-import") (part "22-23-2031"))
    )
    (comp (ref "Y1")
      (value "32.768KHz")
      (footprint "eagle-import:CRYSTAL_CYL_2X6MM_SMT")
      (libsource (lib "eagle-import") (part "CRYSTAL32.768"))
    )
  )
  (nets
    (net (code "1") (name "+3V3") (class "Default")
      (node (ref "C5") (pin "A") (pinfunction "+_A") (pintype "passive"))
      (node (ref "IC1") (pin "2") (pinfunction "OUT_2") (pintype "output"))
      (node (ref "IC1") (pin "4") (pinfunction "OUT_4") (pintype "output"))
      (node (ref "U$3") (pin "VCC") (pinfunction "VCC_VCC") (pintype "bidirectional"))
    )
    (net (code "2") (name "+5V") (class "Default")
      (node (ref "ATMEGA32U4") (pin "14") (pinfunction "VCC_14") (pintype "bidirectional"))
      (node (ref "ATMEGA32U4") (pin "2") (pinfunction "UVCC_2") (pintype "bidirectional"))
      (node (ref "ATMEGA32U4") (pin "24") (pinfunction "AVCC_24") (pintype "bidirectional"))
      (node (ref "ATMEGA32U4") (pin "34") (pinfunction "VCC_34") (pintype "bidirectional"))
      (node (ref "ATMEGA32U4") (pin "44") (pinfunction "AVCC_44") (pintype "bidirectional"))
      (node (ref "ATMEGA32U4") (pin "7") (pinfunction "VBUS_7") (pintype "bidirectional"))
      (node (ref "C1") (pin "+") (pinfunction "+_+") (pintype "passive"))
      (node (ref "C18") (pin "1") (pinfunction "1_1") (pintype "passive"))
      (node (ref "C19") (pin "2") (pinfunction "2_2") (pintype "passive"))
      (node (ref "C3") (pin "1") (pinfunction "1_1") (pintype "passive"))
      (node (ref "C4") (pin "A") (pinfunction "+_A") (pintype "passive"))
      (node (ref "D1") (pin "C") (pinfunction "C_C") (pintype "passive"))
      (node (ref "D10") (pin "A") (pinfunction "A_A") (pintype "passive"))
      (node (ref "D2") (pin "A") (pinfunction "A_A") (pintype "passive"))
      (node (ref "D4") (pin "A") (pinfunction "A_A") (pintype "passive"))
      (node (ref "D6") (pin "A") (pinfunction "A_A") (pintype "passive"))
      (node (ref "D8") (pin "A") (pinfunction "A_A") (pintype "passive"))
      (node (ref "IC1") (pin "3") (pinfunction "IN_3") (pintype "input"))
      (node (ref "IC2") (pin "18") (pinfunction "VDD_18") (pintype "power_in"))
      (node (ref "JP1") (pin "2") (pinfunction "2_2") (pintype "passive"))
      (node (ref "K1") (pin "1") (pinfunction "1_1") (pintype "passive"))
      (node (ref "K2") (pin "1") (pinfunction "1_1") (pintype "passive"))
      (node (ref "K3") (pin "1") (pinfunction "1_1") (pintype "passive"))
      (node (ref "K4") (pin "1") (pinfunction "1_1") (pintype "passive"))
      (node (ref "LED3") (pin "A") (pinfunction "A_A") (pintype "passive"))
      (node (ref "R2") (pin "1") (pinfunction "1_1") (pintype "passive"))
      (node (ref "R6") (pin "2") (pinfunction "2_2") (pintype "passive"))
      (node (ref "RN1") (pin "1") (pinfunction "1_1") (pintype "passive"))
      (node (ref "SMPS_5V@2A") (pin "3") (pinfunction "V+_3") (pintype "input"))
      (node (ref "U$2") (pin "+5V@1") (pinfunction "+5V_+5V@1") (pintype "power_in"))
      (node (ref "X1") (pin "1") (pinfunction "S_1") (pintype "passive"))
    )
    (net (code "3") (name "/(DIN)TE") (class "Default")
      (node (ref "IC2") (pin "14") (pinfunction "A6_14") (pintype "input"))
      (node (ref "U$2") (pin "DATA@1") (pinfunction "DATA_DATA@1") (pintype "input"))
    )
    (net (code "4") (name "/(VT)ADOUT") (class "Default")
      (node (ref "IC2") (pin "17") (pinfunction "A9_17") (pintype "input"))
      (node (ref "R14") (pin "2") (pinfunction "2_2") (pintype "passive"))
    )
    (net (code "5") (name "/A0") (class "Default")
      (node (ref "IC2") (pin "1") (pinfunction "AD11_1") (pintype "input"))
      (node (ref "S1") (pin "16") (pinfunction "16_16") (pintype "passive"))
    )
    (net (code "6") (name "/A1") (class "Default")
      (node (ref "IC2") (pin "2") (pinfunction "AD12_2") (pintype "input"))
      (node (ref "S1") (pin "15") (pinfunction "15_15") (pintype "passive"))
    )
    (net (code "7") (name "/A2") (class "Default")
      (node (ref "IC2") (pin "3") (pinfunction "AD14_3") (pintype "input"))
      (node (ref "S1") (pin "14") (pinfunction "14_14") (pintype "passive"))
    )
    (net (code "8") (name "/A3") (class "Default")
      (node (ref "IC2") (pin "4") (pinfunction "AD15_4") (pintype "input"))
      (node (ref "S1") (pin "13") (pinfunction "13_13") (pintype "passive"))
    )
    (net (code "9") (name "/A4") (class "Default")
      (node (ref "IC2") (pin "5") (pinfunction "DOUT_5") (pintype "input"))
      (node (ref "S1") (pin "12") (pinfunction "12_12") (pintype "passive"))
    )
    (net (code "10") (name "/A5") (class "Default")
      (node (ref "IC2") (pin "6") (pinfunction "TE_6") (pintype "input"))
      (node (ref "S1") (pin "11") (pinfunction "11_11") (pintype "passive"))
    )
    (net (code "11") (name "/A6") (class "Default")
      (node (ref "IC2") (pin "7") (pinfunction "OSC2_7") (pintype "output"))
      (node (ref "S1") (pin "10") (pinfunction "10_10") (pintype "passive"))
    )
    (net (code "12") (name "/A7") (class "Default")
      (node (ref "IC2") (pin "8") (pinfunction "OSC1_8") (pintype "input"))
      (node (ref "S1") (pin "9") (pinfunction "9_9") (pintype "passive"))
    )
    (net (code "13") (name "/BLE_STATUS") (class "Default")
      (node (ref "R3") (pin "2") (pinfunction "2_2") (pintype "passive"))
      (node (ref "U$3") (pin "PIO1") (pinfunction "PIO1_PIO1") (pintype "bidirectional"))
    )
    (net (code "14") (name "/D8") (class "Default")
      (node (ref "ATMEGA32U4") (pin "38") (pinfunction "PF5(ADC5)_38") (pintype "bidirectional"))
      (node (ref "IC2") (pin "10") (pinfunction "A0_10") (pintype "input"))
    )
    (net (code "15") (name "/D9") (class "Default")
      (node (ref "ATMEGA32U4") (pin "39") (pinfunction "PF4(ADC4)_39") (pintype "bidirectional"))
      (node (ref "IC2") (pin "11") (pinfunction "A1_11") (pintype "input"))
    )
    (net (code "16") (name "/D10") (class "Default")
      (node (ref "ATMEGA32U4") (pin "40") (pinfunction "PF1(ADC1)_40") (pintype "bidirectional"))
      (node (ref "IC2") (pin "12") (pinfunction "A2_12") (pintype "input"))
    )
    (net (code "17") (name "/D11") (class "Default")
      (node (ref "ATMEGA32U4") (pin "41") (pinfunction "PF0(ADC0)_41") (pintype "bidirectional"))
      (node (ref "IC2") (pin "13") (pinfunction "A3_13") (pintype "input"))
    )
    (net (code "18") (name "/DOWN") (class "Default")
      (node (ref "ATMEGA32U4") (pin "29") (pinfunction "PB5(ADC12)_29") (pintype "bidirectional"))
      (node (ref "CN2") (pin "7") (pinfunction "S_7") (pintype "passive"))
      (node (ref "RN1") (pin "7") (pinfunction "7_7") (pintype "passive"))
    )
    (net (code "19") (name "/EA0") (class "Default")
      (node (ref "IC3") (pin "1") (pinfunction "AD11_1") (pintype "input"))
      (node (ref "S3") (pin "16") (pinfunction "16_16") (pintype "passive"))
    )
    (net (code "20") (name "/EA1") (class "Default")
      (node (ref "IC3") (pin "2") (pinfunction "AD12_2") (pintype "input"))
      (node (ref "S3") (pin "15") (pinfunction "15_15") (pintype "passive"))
    )
    (net (code "21") (name "/EA2") (class "Default")
      (node (ref "IC3") (pin "3") (pinfunction "AD14_3") (pintype "input"))
      (node (ref "S3") (pin "14") (pinfunction "14_14") (pintype "passive"))
    )
    (net (code "22") (name "/EA3") (class "Default")
      (node (ref "IC3") (pin "4") (pinfunction "AD15_4") (pintype "input"))
      (node (ref "S3") (pin "13") (pinfunction "13_13") (pintype "passive"))
    )
    (net (code "23") (name "/EA4") (class "Default")
      (node (ref "IC3") (pin "5") (pinfunction "DOUT_5") (pintype "input"))
      (node (ref "S3") (pin "12") (pinfunction "12_12") (pintype "passive"))
    )
    (net (code "24") (name "/EA5") (class "Default")
      (node (ref "IC3") (pin "6") (pinfunction "TE_6") (pintype "input"))
      (node (ref "S3") (pin "11") (pinfunction "11_11") (pintype "passive"))
    )
    (net (code "25") (name "/EA6") (class "Default")
      (node (ref "IC3") (pin "7") (pinfunction "OSC2_7") (pintype "output"))
      (node (ref "S3") (pin "10") (pinfunction "10_10") (pintype "passive"))
    )
    (net (code "26") (name "/EA7") (class "Default")
      (node (ref "IC3") (pin "8") (pinfunction "OSC1_8") (pintype "input"))
      (node (ref "S3") (pin "9") (pinfunction "9_9") (pintype "passive"))
    )
    (net (code "27") (name "/EAD8") (class "Default")
      (node (ref "D12") (pin "C") (pinfunction "C_C") (pintype "passive"))
      (node (ref "D14") (pin "C") (pinfunction "C_C") (pintype "passive"))
      (node (ref "D17") (pin "C") (pinfunction "C_C") (pintype "passive"))
      (node (ref "D21") (pin "C") (pinfunction "C_C") (pintype "passive"))
      (node (ref "D25") (pin "C") (pinfunction "C_C") (pintype "passive"))
      (node (ref "D29") (pin "C") (pinfunction "C_C") (pintype "passive"))
      (node (ref "D32") (pin "C") (pinfunction "C_C") (pintype "passive"))
      (node (ref "D38") (pin "C") (pinfunction "C_C") (pintype "passive"))
      (node (ref "IC3") (pin "10") (pinfunction "A0_10") (pintype "input"))
      (node (ref "R9") (pin "1") (pinfunction "1_1") (pintype "passive"))
    )
    (net (code "28") (name "/EAD9") (class "Default")
      (node (ref "IC3") (pin "11") (pinfunction "A1_11") (pintype "input"))
      (node (ref "R21") (pin "1") (pinfunction "1_1") (pintype "passive"))
    )
    (net (code "29") (name "/EAD10") (class "Default")
      (node (ref "D16") (pin "C") (pinfunction "C_C") (pintype "passive"))
      (node (ref "D18") (pin "C") (pinfunction "C_C") (pintype "passive"))
      (node (ref "D20") (pin "C") (pinfunction "C_C") (pintype "passive"))
      (node (ref "D23") (pin "C") (pinfunction "C_C") (pintype "passive"))
      (node (ref "D34") (pin "C") (pinfunction "C_C") (pintype "passive"))
      (node (ref "D36") (pin "C") (pinfunction "C_C") (pintype "passive"))
      (node (ref "D39") (pin "C") (pinfunction "C_C") (pintype "passive"))
      (node (ref "D42") (pin "C") (pinfunction "C_C") (pintype "passive"))
      (node (ref "IC3") (pin "12") (pinfunction "A2_12") (pintype "input"))
      (node (ref "R22") (pin "1") (pinfunction "1_1") (pintype "passive"))
    )
    (net (code "30") (name "/EAD11") (class "Default")
      (node (ref "D24") (pin "C") (pinfunction "C_C") (pintype "passive"))
      (node (ref "D26") (pin "C") (pinfunction "C_C") (pintype "passive"))
      (node (ref "D28") (pin "C") (pinfunction "C_C") (pintype "passive"))
      (node (ref "D31") (pin "C") (pinfunction "C_C") (pintype "passive"))
      (node (ref "D35") (pin "C") (pinfunction "C_C") (pintype "passive"))
      (node (ref "D37") (pin "C") (pinfunction "C_C") (pintype "passive"))
      (node (ref "D40") (pin "C") (pinfunction "C_C") (pintype "passive"))
      (node (ref "D43") (pin "C") (pinfunction "C_C") (pintype "passive"))
      (node (ref "IC3") (pin "13") (pinfunction "A3_13") (pintype "input"))
      (node (ref "R23") (pin "1") (pinfunction "1_1") (pintype "passive"))
    )
    (net (code "31") (name "/EDOUT") (class "Default")
      (node (ref "IC3") (pin "17") (pinfunction "A9_17") (pintype "input"))
      (node (ref "TX") (pin "DATA") (pinfunction "DATA_DATA") (pintype "input"))
    )
    (net (code "32") (name "/EOSC1") (class "Default")
      (node (ref "IC3") (pin "16") (pinfunction "A8_16") (pintype "input"))
      (node (ref "R24") (pin "2") (pinfunction "2_2") (pintype "passive"))
    )
    (net (code "33") (name "/EOSC2") (class "Default")
      (node (ref "IC3") (pin "15") (pinfunction "A7_15") (pintype "input"))
      (node (ref "R24") (pin "1") (pinfunction "1_1") (pintype "passive"))
    )
    (net (code "34") (name "/FAN_ON{slash}OFF") (class "Default")
      (node (ref "ATMEGA32U4") (pin "30") (pinfunction "PB6(ADC13)_30") (pintype "bidirectional"))
      (node (ref "CN2") (pin "8") (pinfunction "S_8") (pintype "passive"))
      (node (ref "RN1") (pin "8") (pinfunction "8_8") (pintype "passive"))
    )
    (net (code "35") (name "/FAN_REG") (class "Default")
      (node (ref "LOAD_CN") (pin "8") (pinfunction "KL_8") (pintype "passive"))
      (node (ref "R10") (pin "1") (pinfunction "1_1") (pintype "passive"))
      (node (ref "R11") (pin "1") (pinfunction "1_1") (pintype "passive"))
      (node (ref "R12") (pin "1") (pinfunction "1_1") (pintype "passive"))
      (node (ref "R13") (pin "1") (pinfunction "1_1") (pintype "passive"))
      (node (ref "T4") (pin "T1") (pinfunction "A1_T1") (pintype "passive"))
      (node (ref "U$5") (pin "1") (pinfunction "1_1") (pintype "passive"))
      (node (ref "U$7") (pin "1") (pinfunction "1_1") (pintype "passive"))
      (node (ref "U$9") (pin "1") (pinfunction "1_1") (pintype "passive"))
    )
    (net (code "36") (name "/LEVEL1") (class "Default")
      (node (ref "ATMEGA32U4") (pin "31") (pinfunction "PC6_31") (pintype "bidirectional"))
      (node (ref "R27") (pin "1") (pinfunction "1_1") (pintype "passive"))
    )
    (net (code "37") (name "/LEVEL2") (class "Default")
      (node (ref "ATMEGA32U4") (pin "32") (pinfunction "PC7_32") (pintype "bidirectional"))
      (node (ref "R29") (pin "1") (pinfunction "1_1") (pintype "passive"))
    )
    (net (code "38") (name "/LEVEL3") (class "Default")
      (node (ref "ATMEGA32U4") (pin "36") (pinfunction "PF7(ADC7)_36") (pintype "bidirectional"))
      (node (ref "R31") (pin "1") (pinfunction "1_1") (pintype "passive"))
    )
    (net (code "39") (name "/LEVEL4") (class "Default")
      (node (ref "ATMEGA32U4") (pin "37") (pinfunction "PF6(ADC6)_37") (pintype "bidirectional"))
      (node (ref "R33") (pin "1") (pinfunction "1_1") (pintype "passive"))
    )
    (net (code "40") (name "/LINE") (class "Default")
      (node (ref "F1") (pin "1") (pinfunction "1_1") (pintype "passive"))
      (node (ref "K1") (pin "C") (pinfunction "P_C") (pintype "passive"))
      (node (ref "K2") (pin "C") (pinfunction "P_C") (pintype "passive"))
      (node (ref "K3") (pin "C") (pinfunction "P_C") (pintype "passive"))
      (node (ref "K4") (pin "C") (pinfunction "P_C") (pintype "passive"))
      (node (ref "LOAD_CN") (pin "1") (pinfunction "KL_1") (pintype "passive"))
      (node (ref "R1") (pin "2") (pinfunction "2_2") (pintype "passive"))
      (node (ref "R10") (pin "2") (pinfunction "2_2") (pintype "passive"))
      (node (ref "R11") (pin "2") (pinfunction "2_2") (pintype "passive"))
      (node (ref "R12") (pin "2") (pinfunction "2_2") (pintype "passive"))
      (node (ref "R13") (pin "2") (pinfunction "2_2") (pintype "passive"))
      (node (ref "R28") (pin "2") (pinfunction "2_2") (pintype "passive"))
      (node (ref "R30") (pin "2") (pinfunction "2_2") (pintype "passive"))
      (node (ref "R32") (pin "2") (pinfunction "2_2") (pintype "passive"))
      (node (ref "R34") (pin "2") (pinfunction "2_2") (pintype "passive"))
      (node (ref "SMPS_5V@2A") (pin "1") (pinfunction "L_1") (pintype "input"))
      (node (ref "T1") (pin "T2") (pinfunction "A2_T2") (pintype "passive"))
      (node (ref "T2") (pin "T2") (pinfunction "A2_T2") (pintype "passive"))
      (node (ref "T3") (pin "T2") (pinfunction "A2_T2") (pintype "passive"))
      (node (ref "T4") (pin "T2") (pinfunction "A2_T2") (pintype "passive"))
    )
    (net (code "41") (name "/LOAD_1") (class "Default")
      (node (ref "K4") (pin "NO") (pinfunction "S_NO") (pintype "passive"))
      (node (ref "LOAD_CN") (pin "4") (pinfunction "KL_4") (pintype "passive"))
    )
    (net (code "42") (name "/LOAD_2") (class "Default")
      (node (ref "K1") (pin "NO") (pinfunction "S_NO") (pintype "passive"))
      (node (ref "LOAD_CN") (pin "5") (pinfunction "KL_5") (pintype "passive"))
    )
    (net (code "43") (name "/LOAD_3") (class "Default")
      (node (ref "K2") (pin "NO") (pinfunction "S_NO") (pintype "passive"))
      (node (ref "LOAD_CN") (pin "6") (pinfunction "KL_6") (pintype "passive"))
    )
    (net (code "44") (name "/MISO") (class "Default")
      (node (ref "ATMEGA32U4") (pin "11") (pinfunction "PB3(MISO)_11") (pintype "bidirectional"))
      (node (ref "JP1") (pin "3") (pinfunction "3_3") (pintype "passive"))
      (node (ref "R20") (pin "1") (pinfunction "1_1") (pintype "passive"))
    )
    (net (code "45") (name "/MOSI") (class "Default")
      (node (ref "ATMEGA32U4") (pin "10") (pinfunction "PB2(MOSI)_10") (pintype "bidirectional"))
      (node (ref "JP1") (pin "5") (pinfunction "5_5") (pintype "passive"))
      (node (ref "R19") (pin "1") (pinfunction "1_1") (pintype "passive"))
    )
    (net (code "46") (name "/N$59") (class "Default")
      (node (ref "D13") (pin "C") (pinfunction "C_C") (pintype "passive"))
      (node (ref "D15") (pin "C") (pinfunction "C_C") (pintype "passive"))
      (node (ref "D19") (pin "C") (pinfunction "C_C") (pintype "passive"))
      (node (ref "D22") (pin "C") (pinfunction "C_C") (pintype "passive"))
      (node (ref "D27") (pin "C") (pinfunction "C_C") (pintype "passive"))
      (node (ref "D30") (pin "C") (pinfunction "C_C") (pintype "passive"))
      (node (ref "D33") (pin "C") (pinfunction "C_C") (pintype "passive"))
      (node (ref "D41") (pin "C") (pinfunction "C_C") (pintype "passive"))
    )
    (net (code "47") (name "/NEUTRAL") (class "Default")
      (node (ref "AC") (pin "2") (pinfunction "KL_2") (pintype "passive"))
      (node (ref "LOAD_CN") (pin "2") (pinfunction "KL_2") (pintype "passive"))
      (node (ref "LOAD_CN") (pin "3") (pinfunction "KL_3") (pintype "passive"))
      (node (ref "R1") (pin "1") (pinfunction "1_1") (pintype "passive"))
      (node (ref "SMPS_5V@2A") (pin "2") (pinfunction "N_2") (pintype "input"))
    )
    (net (code "48") (name "/OSC1") (class "Default")
      (node (ref "IC2") (pin "16") (pinfunction "A8_16") (pintype "input"))
      (node (ref "R16") (pin "1") (pinfunction "1_1") (pintype "passive"))
    )
    (net (code "49") (name "/OSC2") (class "Default")
      (node (ref "IC2") (pin "15") (pinfunction "A7_15") (pintype "input"))
      (node (ref "R16") (pin "2") (pinfunction "2_2") (pintype "passive"))
    )
    (net (code "50") (name "/PLUG_CONTROL") (class "Default")
      (node (ref "K3") (pin "NO") (pinfunction "S_NO") (pintype "passive"))
      (node (ref "LOAD_CN") (pin "7") (pinfunction "KL_7") (pintype "passive"))
    )
    (net (code "51") (name "/RX") (class "Default")
      (node (ref "ATMEGA32U4") (pin "21") (pinfunction "PD3(TX)_21") (pintype "bidirectional"))
      (node (ref "R5") (pin "1") (pinfunction "1_1") (pintype "passive"))
    )
    (net (code "52") (name "/SCK") (class "Default")
      (node (ref "ATMEGA32U4") (pin "9") (pinfunction "PB1(SCK)_9") (pintype "bidirectional"))
      (node (ref "JP1") (pin "4") (pinfunction "4_4") (pintype "passive"))
      (node (ref "R18") (pin "1") (pinfunction "1_1") (pintype "passive"))
    )
    (net (code "53") (name "/SCL") (class "Default")
      (node (ref "ATMEGA32U4") (pin "18") (pinfunction "PD0(SCL)_18") (pintype "bidirectional"))
      (node (ref "R7") (pin "2") (pinfunction "2_2") (pintype "passive"))
      (node (ref "U$1") (pin "6") (pinfunction "SCL_6") (pintype "bidirectional"))
    )
    (net (code "54") (name "/SDA") (class "Default")
      (node (ref "ATMEGA32U4") (pin "19") (pinfunction "PD1(SDA)_19") (pintype "bidirectional"))
      (node (ref "R8") (pin "2") (pinfunction "2_2") (pintype "passive"))
      (node (ref "U$1") (pin "5") (pinfunction "SDA_5") (pintype "bidirectional"))
    )
    (net (code "55") (name "/SW-1") (class "Default")
      (node (ref "ATMEGA32U4") (pin "22") (pinfunction "PD5_22") (pintype "bidirectional"))
      (node (ref "CN2") (pin "2") (pinfunction "S_2") (pintype "passive"))
      (node (ref "RN1") (pin "2") (pinfunction "2_2") (pintype "passive"))
    )
    (net (code "56") (name "/SW-2") (class "Default")
      (node (ref "ATMEGA32U4") (pin "25") (pinfunction "PD4(ADC8)_25") (pintype "bidirectional"))
      (node (ref "CN2") (pin "3") (pinfunction "S_3") (pintype "passive"))
      (node (ref "RN1") (pin "3") (pinfunction "3_3") (pintype "passive"))
    )
    (net (code "57") (name "/SW-3") (class "Default")
      (node (ref "ATMEGA32U4") (pin "26") (pinfunction "PD6(ADC9)_26") (pintype "bidirectional"))
      (node (ref "CN2") (pin "4") (pinfunction "S_4") (pintype "passive"))
      (node (ref "RN1") (pin "4") (pinfunction "4_4") (pintype "passive"))
    )
    (net (code "58") (name "/SW-4") (class "Default")
      (node (ref "ATMEGA32U4") (pin "27") (pinfunction "PD7(ADC10)_27") (pintype "bidirectional"))
      (node (ref "CN2") (pin "5") (pinfunction "S_5") (pintype "passive"))
      (node (ref "RN1") (pin "5") (pinfunction "5_5") (pintype "passive"))
    )
    (net (code "59") (name "/TX") (class "Default")
      (node (ref "ATMEGA32U4") (pin "20") (pinfunction "PD2(RX)_20") (pintype "bidirectional"))
      (node (ref "R4") (pin "1") (pinfunction "1_1") (pintype "passive"))
    )
    (net (code "60") (name "/UP") (class "Default")
      (node (ref "ATMEGA32U4") (pin "28") (pinfunction "PB4(ADC11)_28") (pintype "bidirectional"))
      (node (ref "CN2") (pin "6") (pinfunction "S_6") (pintype "passive"))
      (node (ref "RN1") (pin "6") (pinfunction "6_6") (pintype "passive"))
    )
    (net (code "61") (name "/~{RESET}") (class "Default")
      (node (ref "ATMEGA32U4") (pin "13") (pinfunction "~{RESET}_13") (pintype "bidirectional"))
      (node (ref "JP1") (pin "1") (pinfunction "1_1") (pintype "passive"))
      (node (ref "R6") (pin "1") (pinfunction "1_1") (pintype "passive"))
      (node (ref "U$3") (pin "UART_RTS") (pinfunction "UART_RTS_UART_RTS") (pintype "bidirectional"))
    )
    (net (code "62") (name "GND") (class "Default")
      (node (ref "ATMEGA32U4") (pin "15") (pinfunction "GND_15") (pintype "bidirectional"))
      (node (ref "ATMEGA32U4") (pin "23") (pinfunction "GND_23") (pintype "bidirectional"))
      (node (ref "ATMEGA32U4") (pin "33") (pinfunction "PE2/~{HWB}_33") (pintype "bidirectional"))
      (node (ref "ATMEGA32U4") (pin "35") (pinfunction "GND_35") (pintype "bidirectional"))
      (node (ref "ATMEGA32U4") (pin "43") (pinfunction "GND_43") (pintype "bidirectional"))
      (node (ref "ATMEGA32U4") (pin "5") (pinfunction "UGND_5") (pintype "bidirectional"))
      (node (ref "B1") (pin "-") (pinfunction "-_-") (pintype "passive"))
      (node (ref "C1") (pin "-") (pinfunction "-_-") (pintype "passive"))
      (node (ref "C18") (pin "2") (pinfunction "2_2") (pintype "passive"))
      (node (ref "C19") (pin "1") (pinfunction "1_1") (pintype "passive"))
      (node (ref "C3") (pin "2") (pinfunction "2_2") (pintype "passive"))
      (node (ref "C4") (pin "C") (pinfunction "-_C") (pintype "passive"))
      (node (ref "C5") (pin "C") (pinfunction "-_C") (pintype "passive"))
      (node (ref "C6") (pin "2") (pinfunction "2_2") (pintype "passive"))
      (node (ref "C7") (pin "1") (pinfunction "1_1") (pintype "passive"))
      (node (ref "C8") (pin "1") (pinfunction "1_1") (pintype "passive"))
      (node (ref "C9") (pin "1") (pinfunction "1_1") (pintype "passive"))
      (node (ref "CN2") (pin "1") (pinfunction "S_1") (pintype "passive"))
      (node (ref "D1") (pin "A") (pinfunction "A_A") (pintype "passive"))
      (node (ref "IC1") (pin "1") (pinfunction "ADJ_1") (pintype "input"))
      (node (ref "IC2") (pin "9") (pinfunction "VSS_9") (pintype "power_in"))
      (node (ref "JP1") (pin "6") (pinfunction "6_6") (pintype "passive"))
      (node (ref "LED1") (pin "C") (pinfunction "C_C") (pintype "passive"))
      (node (ref "LED2") (pin "C") (pinfunction "C_C") (pintype "passive"))
      (node (ref "OK1") (pin "2") (pinfunction "C_2") (pintype "passive"))
      (node (ref "OK2") (pin "2") (pinfunction "C_2") (pintype "passive"))
      (node (ref "OK3") (pin "2") (pinfunction "C_2") (pintype "passive"))
      (node (ref "OK4") (pin "2") (pinfunction "C_2") (pintype "passive"))
      (node (ref "OK5") (pin "2") (pinfunction "C_2") (pintype "passive"))
      (node (ref "OK6") (pin "2") (pinfunction "C_2") (pintype "passive"))
      (node (ref "OK7") (pin "2") (pinfunction "C_2") (pintype "passive"))
      (node (ref "OK8") (pin "2") (pinfunction "C_2") (pintype "passive"))
      (node (ref "Q2") (pin "2") (pinfunction "E_2") (pintype "passive"))
      (node (ref "Q3") (pin "2") (pinfunction "E_2") (pintype "passive"))
      (node (ref "Q4") (pin "2") (pinfunction "E_2") (pintype "passive"))
      (node (ref "Q5") (pin "2") (pinfunction "E_2") (pintype "passive"))
      (node (ref "Q6") (pin "2") (pinfunction "E_2") (pintype "passive"))
      (node (ref "S1") (pin "1") (pinfunction "1_1") (pintype "passive"))
      (node (ref "S1") (pin "2") (pinfunction "2_2") (pintype "passive"))
      (node (ref "S1") (pin "3") (pinfunction "3_3") (pintype "passive"))
      (node (ref "S1") (pin "4") (pinfunction "4_4") (pintype "passive"))
      (node (ref "S1") (pin "5") (pinfunction "5_5") (pintype "passive"))
      (node (ref "S1") (pin "6") (pinfunction "6_6") (pintype "passive"))
      (node (ref "S1") (pin "7") (pinfunction "7_7") (pintype "passive"))
      (node (ref "S1") (pin "8") (pinfunction "8_8") (pintype "passive"))
      (node (ref "SMPS_5V@2A") (pin "4") (pinfunction "GND_4") (pintype "input"))
      (node (ref "U$1") (pin "4") (pinfunction "GND_4") (pintype "bidirectional"))
      (node (ref "U$2") (pin "GND@1") (pinfunction "GND_GND@1") (pintype "power_in"))
      (node (ref "U$3") (pin "GND") (pinfunction "GND_GND") (pintype "bidirectional"))
      (node (ref "X1") (pin "2") (pinfunction "S_2") (pintype "passive"))
    )
    (net (code "63") (name "GNDA") (class "Default")
      (node (ref "IC3") (pin "14") (pinfunction "A6_14") (pintype "input"))
      (node (ref "IC3") (pin "9") (pinfunction "VSS_9") (pintype "power_in"))
      (node (ref "R21") (pin "2") (pinfunction "2_2") (pintype "passive"))
      (node (ref "R22") (pin "2") (pinfunction "2_2") (pintype "passive"))
      (node (ref "R23") (pin "2") (pinfunction "2_2") (pintype "passive"))
      (node (ref "R9") (pin "2") (pinfunction "2_2") (pintype "passive"))
      (node (ref "S3") (pin "1") (pinfunction "1_1") (pintype "passive"))
      (node (ref "S3") (pin "2") (pinfunction "2_2") (pintype "passive"))
      (node (ref "S3") (pin "3") (pinfunction "3_3") (pintype "passive"))
      (node (ref "S3") (pin "4") (pinfunction "4_4") (pintype "passive"))
      (node (ref "S3") (pin "5") (pinfunction "5_5") (pintype "passive"))
      (node (ref "S3") (pin "6") (pinfunction "6_6") (pintype "passive"))
      (node (ref "S3") (pin "7") (pinfunction "7_7") (pintype "passive"))
      (node (ref "S3") (pin "8") (pinfunction "8_8") (pintype "passive"))
      (node (ref "TX") (pin "GND") (pinfunction "GND_GND") (pintype "power_in"))
      (node (ref "VBAT") (pin "2") (pinfunction "-_2") (pintype "power_in"))
    )
    (net (code "64") (name "Net-(0-Pad2)") (class "Default")
      (node (ref "0") (pin "2") (pinfunction "2_2") (pintype "passive"))
      (node (ref "D27") (pin "A") (pinfunction "A_A") (pintype "passive"))
      (node (ref "D28") (pin "A") (pinfunction "A_A") (pintype "passive"))
    )
    (net (code "65") (name "Net-(1-Pad2)") (class "Default")
      (node (ref "1") (pin "2") (pinfunction "2_2") (pintype "passive"))
      (node (ref "D12") (pin "A") (pinfunction "A_A") (pintype "passive"))
    )
    (net (code "66") (name "Net-(2-Pad2)") (class "Default")
      (node (ref "2") (pin "2") (pinfunction "2_2") (pintype "passive"))
      (node (ref "D13") (pin "A") (pinfunction "A_A") (pintype "passive"))
    )
    (net (code "67") (name "Net-(3-Pad2)") (class "Default")
      (node (ref "3") (pin "2") (pinfunction "2_2") (pintype "passive"))
      (node (ref "D14") (pin "A") (pinfunction "A_A") (pintype "passive"))
      (node (ref "D15") (pin "A") (pinfunction "A_A") (pintype "passive"))
    )
    (net (code "68") (name "Net-(4-Pad2)") (class "Default")
      (node (ref "4") (pin "2") (pinfunction "2_2") (pintype "passive"))
      (node (ref "D16") (pin "A") (pinfunction "A_A") (pintype "passive"))
    )
    (net (code "69") (name "Net-(5-Pad2)") (class "Default")
      (node (ref "5") (pin "2") (pinfunction "2_2") (pintype "passive"))
      (node (ref "D17") (pin "A") (pinfunction "A_A") (pintype "passive"))
      (node (ref "D18") (pin "A") (pinfunction "A_A") (pintype "passive"))
    )
    (net (code "70") (name "Net-(6-Pad2)") (class "Default")
      (node (ref "6") (pin "2") (pinfunction "2_2") (pintype "passive"))
      (node (ref "D19") (pin "A") (pinfunction "A_A") (pintype "passive"))
      (node (ref "D20") (pin "A") (pinfunction "A_A") (pintype "passive"))
    )
    (net (code "71") (name "Net-(7-Pad2)") (class "Default")
      (node (ref "7") (pin "2") (pinfunction "2_2") (pintype "passive"))
      (node (ref "D21") (pin "A") (pinfunction "A_A") (pintype "passive"))
      (node (ref "D22") (pin "A") (pinfunction "A_A") (pintype "passive"))
      (node (ref "D23") (pin "A") (pinfunction "A_A") (pintype "passive"))
    )
    (net (code "72") (name "Net-(8-Pad2)") (class "Default")
      (node (ref "8") (pin "2") (pinfunction "2_2") (pintype "passive"))
      (node (ref "D24") (pin "A") (pinfunction "A_A") (pintype "passive"))
    )
    (net (code "73") (name "Net-(9-Pad2)") (class "Default")
      (node (ref "9") (pin "2") (pinfunction "2_2") (pintype "passive"))
      (node (ref "D25") (pin "A") (pinfunction "A_A") (pintype "passive"))
      (node (ref "D26") (pin "A") (pinfunction "A_A") (pintype "passive"))
    )
    (net (code "74") (name "Net-(ACA-KL)") (class "Default")
      (node (ref "AC") (pin "1") (pinfunction "KL_1") (pintype "passive"))
      (node (ref "F1") (pin "2") (pinfunction "2_2") (pintype "passive"))
    )
    (net (code "75") (name "Net-(ANT1-Pad1)") (class "Default")
      (node (ref "ANT1") (pin "1") (pinfunction "1_1") (pintype "output"))
      (node (ref "U$2") (pin "ANT") (pinfunction "ANT_ANT") (pintype "passive"))
    )
    (net (code "76") (name "Net-(ANT2-Pad1)") (class "Default")
      (node (ref "ANT2") (pin "1") (pinfunction "1_1") (pintype "output"))
      (node (ref "TX") (pin "ANT") (pinfunction "ANT_ANT") (pintype "passive"))
    )
    (net (code "77") (name "Net-(ATMEGA32U4-AREF)") (class "Default")
      (node (ref "ATMEGA32U4") (pin "42") (pinfunction "AREF_42") (pintype "bidirectional"))
      (node (ref "C6") (pin "1") (pinfunction "1_1") (pintype "passive"))
    )
    (net (code "78") (name "Net-(ATMEGA32U4-PB0(SS))") (class "Default")
      (node (ref "ATMEGA32U4") (pin "8") (pinfunction "PB0(SS)_8") (pintype "bidirectional"))
      (node (ref "R17") (pin "1") (pinfunction "1_1") (pintype "passive"))
    )
    (net (code "79") (name "Net-(ATMEGA32U4-UCAP)") (class "Default")
      (node (ref "ATMEGA32U4") (pin "6") (pinfunction "UCAP_6") (pintype "bidirectional"))
      (node (ref "C7") (pin "2") (pinfunction "2_2") (pintype "passive"))
    )
    (net (code "80") (name "Net-(ATMEGA32U4-XTAL1)") (class "Default")
      (node (ref "ATMEGA32U4") (pin "17") (pinfunction "XTAL1_17") (pintype "bidirectional"))
      (node (ref "C9") (pin "2") (pinfunction "2_2") (pintype "passive"))
      (node (ref "Q1") (pin "1") (pinfunction "1_1") (pintype "passive"))
    )
    (net (code "81") (name "Net-(ATMEGA32U4-XTAL2)") (class "Default")
      (node (ref "ATMEGA32U4") (pin "16") (pinfunction "XTAL2_16") (pintype "bidirectional"))
      (node (ref "C8") (pin "2") (pinfunction "2_2") (pintype "passive"))
      (node (ref "Q1") (pin "2") (pinfunction "2_2") (pintype "passive"))
    )
    (net (code "82") (name "Net-(B1-Pad+)") (class "Default")
      (node (ref "B1") (pin "+") (pinfunction "+_+") (pintype "passive"))
      (node (ref "D3") (pin "A") (pinfunction "A_A") (pintype "passive"))
    )
    (net (code "83") (name "Net-(C14-Pad2)") (class "Default")
      (node (ref "C14") (pin "2") (pinfunction "2_2") (pintype "passive"))
      (node (ref "U$4") (pin "1") (pinfunction "1_1") (pintype "passive"))
      (node (ref "U$5") (pin "2") (pinfunction "2_2") (pintype "passive"))
    )
    (net (code "84") (name "Net-(C15-Pad2)") (class "Default")
      (node (ref "C15") (pin "2") (pinfunction "2_2") (pintype "passive"))
      (node (ref "U$6") (pin "1") (pinfunction "1_1") (pintype "passive"))
      (node (ref "U$7") (pin "2") (pinfunction "2_2") (pintype "passive"))
    )
    (net (code "85") (name "Net-(C16-Pad2)") (class "Default")
      (node (ref "C16") (pin "2") (pinfunction "2_2") (pintype "passive"))
      (node (ref "C17") (pin "2") (pinfunction "2_2") (pintype "passive"))
      (node (ref "U$8") (pin "1") (pinfunction "1_1") (pintype "passive"))
      (node (ref "U$9") (pin "2") (pinfunction "2_2") (pintype "passive"))
    )
    (net (code "86") (name "Net-(D4-PadC)") (class "Default")
      (node (ref "D4") (pin "C") (pinfunction "C_C") (pintype "passive"))
      (node (ref "D5") (pin "C") (pinfunction "C_C") (pintype "passive"))
    )
    (net (code "87") (name "Net-(D6-PadC)") (class "Default")
      (node (ref "D6") (pin "C") (pinfunction "C_C") (pintype "passive"))
      (node (ref "D7") (pin "C") (pinfunction "C_C") (pintype "passive"))
    )
    (net (code "88") (name "Net-(D8-PadC)") (class "Default")
      (node (ref "D8") (pin "C") (pinfunction "C_C") (pintype "passive"))
      (node (ref "D9") (pin "C") (pinfunction "C_C") (pintype "passive"))
    )
    (net (code "89") (name "Net-(D10-PadC)") (class "Default")
      (node (ref "D10") (pin "C") (pinfunction "C_C") (pintype "passive"))
      (node (ref "D11") (pin "C") (pinfunction "C_C") (pintype "passive"))
    )
    (net (code "90") (name "Net-(D29-PadA)") (class "Default")
      (node (ref "D29") (pin "A") (pinfunction "A_A") (pintype "passive"))
      (node (ref "D30") (pin "A") (pinfunction "A_A") (pintype "passive"))
      (node (ref "D31") (pin "A") (pinfunction "A_A") (pintype "passive"))
      (node (ref "UP") (pin "2") (pinfunction "2_2") (pintype "passive"))
    )
    (net (code "91") (name "Net-(D32-PadA)") (class "Default")
      (node (ref "D32") (pin "A") (pinfunction "A_A") (pintype "passive"))
      (node (ref "D33") (pin "A") (pinfunction "A_A") (pintype "passive"))
      (node (ref "D34") (pin "A") (pinfunction "A_A") (pintype "passive"))
      (node (ref "D35") (pin "A") (pinfunction "A_A") (pintype "passive"))
      (node (ref "MASTER") (pin "2") (pinfunction "2_2") (pintype "passive"))
    )
    (net (code "92") (name "Net-(D36-PadA)") (class "Default")
      (node (ref "D36") (pin "A") (pinfunction "A_A") (pintype "passive"))
      (node (ref "D37") (pin "A") (pinfunction "A_A") (pintype "passive"))
      (node (ref "F_ON") (pin "2") (pinfunction "2_2") (pintype "passive"))
    )
    (net (code "93") (name "Net-(D38-PadA)") (class "Default")
      (node (ref "D38") (pin "A") (pinfunction "A_A") (pintype "passive"))
      (node (ref "D39") (pin "A") (pinfunction "A_A") (pintype "passive"))
      (node (ref "D40") (pin "A") (pinfunction "A_A") (pintype "passive"))
      (node (ref "DOWN") (pin "2") (pinfunction "2_2") (pintype "passive"))
    )
    (net (code "94") (name "Net-(D41-PadA)") (class "Default")
      (node (ref "D41") (pin "A") (pinfunction "A_A") (pintype "passive"))
      (node (ref "D42") (pin "A") (pinfunction "A_A") (pintype "passive"))
      (node (ref "D43") (pin "A") (pinfunction "A_A") (pintype "passive"))
      (node (ref "F_OFF") (pin "2") (pinfunction "2_2") (pintype "passive"))
    )
    (net (code "95") (name "Net-(LED1-PadA)") (class "Default")
      (node (ref "LED1") (pin "A") (pinfunction "A_A") (pintype "passive"))
      (node (ref "R2") (pin "2") (pinfunction "2_2") (pintype "passive"))
    )
    (net (code "96") (name "Net-(LED2-PadA)") (class "Default")
      (node (ref "LED2") (pin "A") (pinfunction "A_A") (pintype "passive"))
      (node (ref "R3") (pin "1") (pinfunction "1_1") (pintype "passive"))
    )
    (net (code "97") (name "Net-(LED3-PadC)") (class "Default")
      (node (ref "LED3") (pin "C") (pinfunction "C_C") (pintype "passive"))
      (node (ref "R15") (pin "2") (pinfunction "2_2") (pintype "passive"))
    )
    (net (code "98") (name "Net-(OK1-A)") (class "Default")
      (node (ref "OK1") (pin "1") (pinfunction "A_1") (pintype "passive"))
      (node (ref "R17") (pin "2") (pinfunction "2_2") (pintype "passive"))
    )
    (net (code "99") (name "Net-(OK1-COL)") (class "Default")
      (node (ref "D5") (pin "A") (pinfunction "A_A") (pintype "passive"))
      (node (ref "K1") (pin "2") (pinfunction "2_2") (pintype "passive"))
      (node (ref "OK1") (pin "4") (pinfunction "COL_4") (pintype "passive"))
      (node (ref "Q3") (pin "3") (pinfunction "C_3") (pintype "passive"))
    )
    (net (code "100") (name "Net-(OK1-EMIT)") (class "Default")
      (node (ref "OK1") (pin "3") (pinfunction "EMIT_3") (pintype "passive"))
      (node (ref "Q3") (pin "1") (pinfunction "B_1") (pintype "passive"))
    )
    (net (code "101") (name "Net-(OK2-A)") (class "Default")
      (node (ref "OK2") (pin "1") (pinfunction "A_1") (pintype "passive"))
      (node (ref "R18") (pin "2") (pinfunction "2_2") (pintype "passive"))
    )
    (net (code "102") (name "Net-(OK2-COL)") (class "Default")
      (node (ref "D7") (pin "A") (pinfunction "A_A") (pintype "passive"))
      (node (ref "K2") (pin "2") (pinfunction "2_2") (pintype "passive"))
      (node (ref "OK2") (pin "4") (pinfunction "COL_4") (pintype "passive"))
      (node (ref "Q4") (pin "3") (pinfunction "C_3") (pintype "passive"))
    )
    (net (code "103") (name "Net-(OK2-EMIT)") (class "Default")
      (node (ref "OK2") (pin "3") (pinfunction "EMIT_3") (pintype "passive"))
      (node (ref "Q4") (pin "1") (pinfunction "B_1") (pintype "passive"))
    )
    (net (code "104") (name "Net-(OK3-A)") (class "Default")
      (node (ref "OK3") (pin "1") (pinfunction "A_1") (pintype "passive"))
      (node (ref "R19") (pin "2") (pinfunction "2_2") (pintype "passive"))
    )
    (net (code "105") (name "Net-(OK3-COL)") (class "Default")
      (node (ref "D9") (pin "A") (pinfunction "A_A") (pintype "passive"))
      (node (ref "K3") (pin "2") (pinfunction "2_2") (pintype "passive"))
      (node (ref "OK3") (pin "4") (pinfunction "COL_4") (pintype "passive"))
      (node (ref "Q5") (pin "3") (pinfunction "C_3") (pintype "passive"))
    )
    (net (code "106") (name "Net-(OK3-EMIT)") (class "Default")
      (node (ref "OK3") (pin "3") (pinfunction "EMIT_3") (pintype "passive"))
      (node (ref "Q5") (pin "1") (pinfunction "B_1") (pintype "passive"))
    )
    (net (code "107") (name "Net-(OK4-A)") (class "Default")
      (node (ref "OK4") (pin "1") (pinfunction "A_1") (pintype "passive"))
      (node (ref "R27") (pin "2") (pinfunction "2_2") (pintype "passive"))
    )
    (net (code "108") (name "Net-(OK4-A1)") (class "Default")
      (node (ref "OK4") (pin "4") (pinfunction "A1_4") (pintype "passive"))
      (node (ref "T1") (pin "G") (pinfunction "G_G") (pintype "passive"))
    )
    (net (code "109") (name "Net-(OK4-A2)") (class "Default")
      (node (ref "OK4") (pin "6") (pinfunction "A2_6") (pintype "passive"))
      (node (ref "R28") (pin "1") (pinfunction "1_1") (pintype "passive"))
    )
    (net (code "110") (name "Net-(OK5-A)") (class "Default")
      (node (ref "OK5") (pin "1") (pinfunction "A_1") (pintype "passive"))
      (node (ref "R29") (pin "2") (pinfunction "2_2") (pintype "passive"))
    )
    (net (code "111") (name "Net-(OK5-A1)") (class "Default")
      (node (ref "OK5") (pin "4") (pinfunction "A1_4") (pintype "passive"))
      (node (ref "T2") (pin "G") (pinfunction "G_G") (pintype "passive"))
    )
    (net (code "112") (name "Net-(OK5-A2)") (class "Default")
      (node (ref "OK5") (pin "6") (pinfunction "A2_6") (pintype "passive"))
      (node (ref "R30") (pin "1") (pinfunction "1_1") (pintype "passive"))
    )
    (net (code "113") (name "Net-(OK6-A)") (class "Default")
      (node (ref "OK6") (pin "1") (pinfunction "A_1") (pintype "passive"))
      (node (ref "R31") (pin "2") (pinfunction "2_2") (pintype "passive"))
    )
    (net (code "114") (name "Net-(OK6-A1)") (class "Default")
      (node (ref "OK6") (pin "4") (pinfunction "A1_4") (pintype "passive"))
      (node (ref "T3") (pin "G") (pinfunction "G_G") (pintype "passive"))
    )
    (net (code "115") (name "Net-(OK6-A2)") (class "Default")
      (node (ref "OK6") (pin "6") (pinfunction "A2_6") (pintype "passive"))
      (node (ref "R32") (pin "1") (pinfunction "1_1") (pintype "passive"))
    )
    (net (code "116") (name "Net-(OK7-A)") (class "Default")
      (node (ref "OK7") (pin "1") (pinfunction "A_1") (pintype "passive"))
      (node (ref "R33") (pin "2") (pinfunction "2_2") (pintype "passive"))
    )
    (net (code "117") (name "Net-(OK7-A1)") (class "Default")
      (node (ref "OK7") (pin "4") (pinfunction "A1_4") (pintype "passive"))
      (node (ref "T4") (pin "G") (pinfunction "G_G") (pintype "passive"))
    )
    (net (code "118") (name "Net-(OK7-A2)") (class "Default")
      (node (ref "OK7") (pin "6") (pinfunction "A2_6") (pintype "passive"))
      (node (ref "R34") (pin "1") (pinfunction "1_1") (pintype "passive"))
    )
    (net (code "119") (name "Net-(OK8-A)") (class "Default")
      (node (ref "OK8") (pin "1") (pinfunction "A_1") (pintype "passive"))
      (node (ref "R20") (pin "2") (pinfunction "2_2") (pintype "passive"))
    )
    (net (code "120") (name "Net-(OK8-COL)") (class "Default")
      (node (ref "D11") (pin "A") (pinfunction "A_A") (pintype "passive"))
      (node (ref "K4") (pin "2") (pinfunction "2_2") (pintype "passive"))
      (node (ref "OK8") (pin "4") (pinfunction "COL_4") (pintype "passive"))
      (node (ref "Q6") (pin "3") (pinfunction "C_3") (pintype "passive"))
    )
    (net (code "121") (name "Net-(OK8-EMIT)") (class "Default")
      (node (ref "OK8") (pin "3") (pinfunction "EMIT_3") (pintype "passive"))
      (node (ref "Q6") (pin "1") (pinfunction "B_1") (pintype "passive"))
    )
    (net (code "122") (name "Net-(Q2-B)") (class "Default")
      (node (ref "Q2") (pin "1") (pinfunction "B_1") (pintype "passive"))
      (node (ref "R14") (pin "1") (pinfunction "1_1") (pintype "passive"))
    )
    (net (code "123") (name "Net-(Q2-C)") (class "Default")
      (node (ref "Q2") (pin "3") (pinfunction "C_3") (pintype "passive"))
      (node (ref "R15") (pin "1") (pinfunction "1_1") (pintype "passive"))
    )
    (net (code "124") (name "Net-(R4-Pad2)") (class "Default")
      (node (ref "R4") (pin "2") (pinfunction "2_2") (pintype "passive"))
      (node (ref "U$3") (pin "UART_TX") (pinfunction "UART_TX_UART_TX") (pintype "bidirectional"))
    )
    (net (code "125") (name "Net-(R5-Pad2)") (class "Default")
      (node (ref "R5") (pin "2") (pinfunction "2_2") (pintype "passive"))
      (node (ref "U$3") (pin "UART_RX") (pinfunction "UART_RX_UART_RX") (pintype "bidirectional"))
    )
    (net (code "126") (name "Net-(S2-P)") (class "Default")
      (node (ref "S2") (pin "2") (pinfunction "P_2") (pintype "passive"))
      (node (ref "VBAT") (pin "1") (pinfunction "+_1") (pintype "power_in"))
    )
    (net (code "127") (name "Net-(S2-S)") (class "Default")
      (node (ref "S2") (pin "3") (pinfunction "S_3") (pintype "passive"))
      (node (ref "TX") (pin "VCC") (pinfunction "+5V_VCC") (pintype "power_in"))
    )
    (net (code "128") (name "Net-(T1-A1)") (class "Default")
      (node (ref "C14") (pin "1") (pinfunction "1_1") (pintype "passive"))
      (node (ref "T1") (pin "T1") (pinfunction "A1_T1") (pintype "passive"))
      (node (ref "U$4") (pin "2") (pinfunction "2_2") (pintype "passive"))
    )
    (net (code "129") (name "Net-(T2-A1)") (class "Default")
      (node (ref "C15") (pin "1") (pinfunction "1_1") (pintype "passive"))
      (node (ref "T2") (pin "T1") (pinfunction "A1_T1") (pintype "passive"))
      (node (ref "U$6") (pin "2") (pinfunction "2_2") (pintype "passive"))
    )
    (net (code "130") (name "Net-(T3-A1)") (class "Default")
      (node (ref "C16") (pin "1") (pinfunction "1_1") (pintype "passive"))
      (node (ref "C17") (pin "1") (pinfunction "1_1") (pintype "passive"))
      (node (ref "T3") (pin "T1") (pinfunction "A1_T1") (pintype "passive"))
      (node (ref "U$8") (pin "2") (pinfunction "2_2") (pintype "passive"))
    )
    (net (code "131") (name "Net-(U$1-VBATT)") (class "Default")
      (node (ref "D2") (pin "C") (pinfunction "C_C") (pintype "passive"))
      (node (ref "D3") (pin "C") (pinfunction "C_C") (pintype "passive"))
      (node (ref "R7") (pin "1") (pinfunction "1_1") (pintype "passive"))
      (node (ref "R8") (pin "1") (pinfunction "1_1") (pintype "passive"))
      (node (ref "U$1") (pin "3") (pinfunction "VBATT_3") (pintype "bidirectional"))
      (node (ref "U$1") (pin "8") (pinfunction "VCC_8") (pintype "bidirectional"))
    )
    (net (code "132") (name "Net-(U$1-X1)") (class "Default")
      (node (ref "U$1") (pin "1") (pinfunction "X1_1") (pintype "bidirectional"))
      (node (ref "Y1") (pin "1") (pinfunction "1_1") (pintype "passive"))
    )
    (net (code "133") (name "Net-(U$1-X2)") (class "Default")
      (node (ref "U$1") (pin "2") (pinfunction "X2_2") (pintype "bidirectional"))
      (node (ref "Y1") (pin "2") (pinfunction "2_2") (pintype "passive"))
    )
    (net (code "134") (name "V+") (class "Default")
      (node (ref "0") (pin "1") (pinfunction "1_1") (pintype "passive"))
      (node (ref "1") (pin "1") (pinfunction "1_1") (pintype "passive"))
      (node (ref "2") (pin "1") (pinfunction "1_1") (pintype "passive"))
      (node (ref "3") (pin "1") (pinfunction "1_1") (pintype "passive"))
      (node (ref "4") (pin "1") (pinfunction "1_1") (pintype "passive"))
      (node (ref "5") (pin "1") (pinfunction "1_1") (pintype "passive"))
      (node (ref "6") (pin "1") (pinfunction "1_1") (pintype "passive"))
      (node (ref "7") (pin "1") (pinfunction "1_1") (pintype "passive"))
      (node (ref "8") (pin "1") (pinfunction "1_1") (pintype "passive"))
      (node (ref "9") (pin "1") (pinfunction "1_1") (pintype "passive"))
      (node (ref "DOWN") (pin "1") (pinfunction "1_1") (pintype "passive"))
      (node (ref "F_OFF") (pin "1") (pinfunction "1_1") (pintype "passive"))
      (node (ref "F_ON") (pin "1") (pinfunction "1_1") (pintype "passive"))
      (node (ref "IC3") (pin "18") (pinfunction "VDD_18") (pintype "power_in"))
      (node (ref "MASTER") (pin "1") (pinfunction "1_1") (pintype "passive"))
      (node (ref "UP") (pin "1") (pinfunction "1_1") (pintype "passive"))
    )
    (net (code "135") (name "unconnected-(ATMEGA32U4-D+-Pad4)") (class "Default")
      (node (ref "ATMEGA32U4") (pin "4") (pinfunction "D+_4") (pintype "bidirectional"))
    )
    (net (code "136") (name "unconnected-(ATMEGA32U4-D--Pad3)") (class "Default")
      (node (ref "ATMEGA32U4") (pin "3") (pinfunction "D-_3") (pintype "bidirectional"))
    )
    (net (code "137") (name "unconnected-(ATMEGA32U4-PB7-Pad12)") (class "Default")
      (node (ref "ATMEGA32U4") (pin "12") (pinfunction "PB7_12") (pintype "bidirectional"))
    )
    (net (code "138") (name "unconnected-(ATMEGA32U4-PE6-Pad1)") (class "Default")
      (node (ref "ATMEGA32U4") (pin "1") (pinfunction "PE6_1") (pintype "bidirectional"))
    )
    (net (code "139") (name "unconnected-(K1B-O-PadNC)") (class "Default")
      (node (ref "K1") (pin "NC") (pinfunction "O_NC") (pintype "passive"))
    )
    (net (code "140") (name "unconnected-(K2B-O-PadNC)") (class "Default")
      (node (ref "K2") (pin "NC") (pinfunction "O_NC") (pintype "passive"))
    )
    (net (code "141") (name "unconnected-(K3B-O-PadNC)") (class "Default")
      (node (ref "K3") (pin "NC") (pinfunction "O_NC") (pintype "passive"))
    )
    (net (code "142") (name "unconnected-(K4B-O-PadNC)") (class "Default")
      (node (ref "K4") (pin "NC") (pinfunction "O_NC") (pintype "passive"))
    )
    (net (code "143") (name "unconnected-(S2-O-Pad1)") (class "Default")
      (node (ref "S2") (pin "1") (pinfunction "O_1") (pintype "passive"))
    )
    (net (code "144") (name "unconnected-(U$1-SQW-Pad7)") (class "Default")
      (node (ref "U$1") (pin "7") (pinfunction "SQW_7") (pintype "bidirectional"))
    )
    (net (code "145") (name "unconnected-(U$3-PadNC1)") (class "Default")
      (node (ref "U$3") (pin "NC1") (pinfunction "NC1_NC1") (pintype "bidirectional"))
    )
    (net (code "146") (name "unconnected-(U$3-PadNC2)") (class "Default")
      (node (ref "U$3") (pin "NC2") (pinfunction "NC2_NC2") (pintype "bidirectional"))
    )
    (net (code "147") (name "unconnected-(U$3-PadNC3)") (class "Default")
      (node (ref "U$3") (pin "NC3") (pinfunction "NC3_NC3") (pintype "bidirectional"))
    )
    (net (code "148") (name "unconnected-(U$3-PadNV1)") (class "Default")
      (node (ref "U$3") (pin "NV1") (pinfunction "NV1_NV1") (pintype "bidirectional"))
    )
    (net (code "149") (name "unconnected-(U$3-PadNV2)") (class "Default")
      (node (ref "U$3") (pin "NV2") (pinfunction "NV2_NV2") (pintype "bidirectional"))
    )
    (net (code "150") (name "unconnected-(U$3-PadPIO0)") (class "Default")
      (node (ref "U$3") (pin "PIO0") (pinfunction "PIO0_PIO0") (pintype "bidirectional"))
    )
    (net (code "151") (name "unconnected-(U$3-PadPIO2)") (class "Default")
      (node (ref "U$3") (pin "PIO2") (pinfunction "PIO2_PIO2") (pintype "bidirectional"))
    )
    (net (code "152") (name "unconnected-(U$3-PadPIO3)") (class "Default")
      (node (ref "U$3") (pin "PIO3") (pinfunction "PIO3_PIO3") (pintype "bidirectional"))
    )
    (net (code "153") (name "unconnected-(U$3-PadRESETB)") (class "Default")
      (node (ref "U$3") (pin "RESETB") (pinfunction "RESETB_RESETB") (pintype "bidirectional"))
    )
    (net (code "154") (name "unconnected-(U$3-PadUART_CTS)") (class "Default")
      (node (ref "U$3") (pin "UART_CTS") (pinfunction "UART_CTS_UART_CTS") (pintype "bidirectional"))
    )
    (net (code "155") (name "unconnected-(X1C-S-Pad3)") (class "Default")
      (node (ref "X1") (pin "3") (pinfunction "S_3") (pintype "passive"))
    )
  )
)
